# Sheet_1.net
KiCad netlist of a schematic drawn in Altium Designer
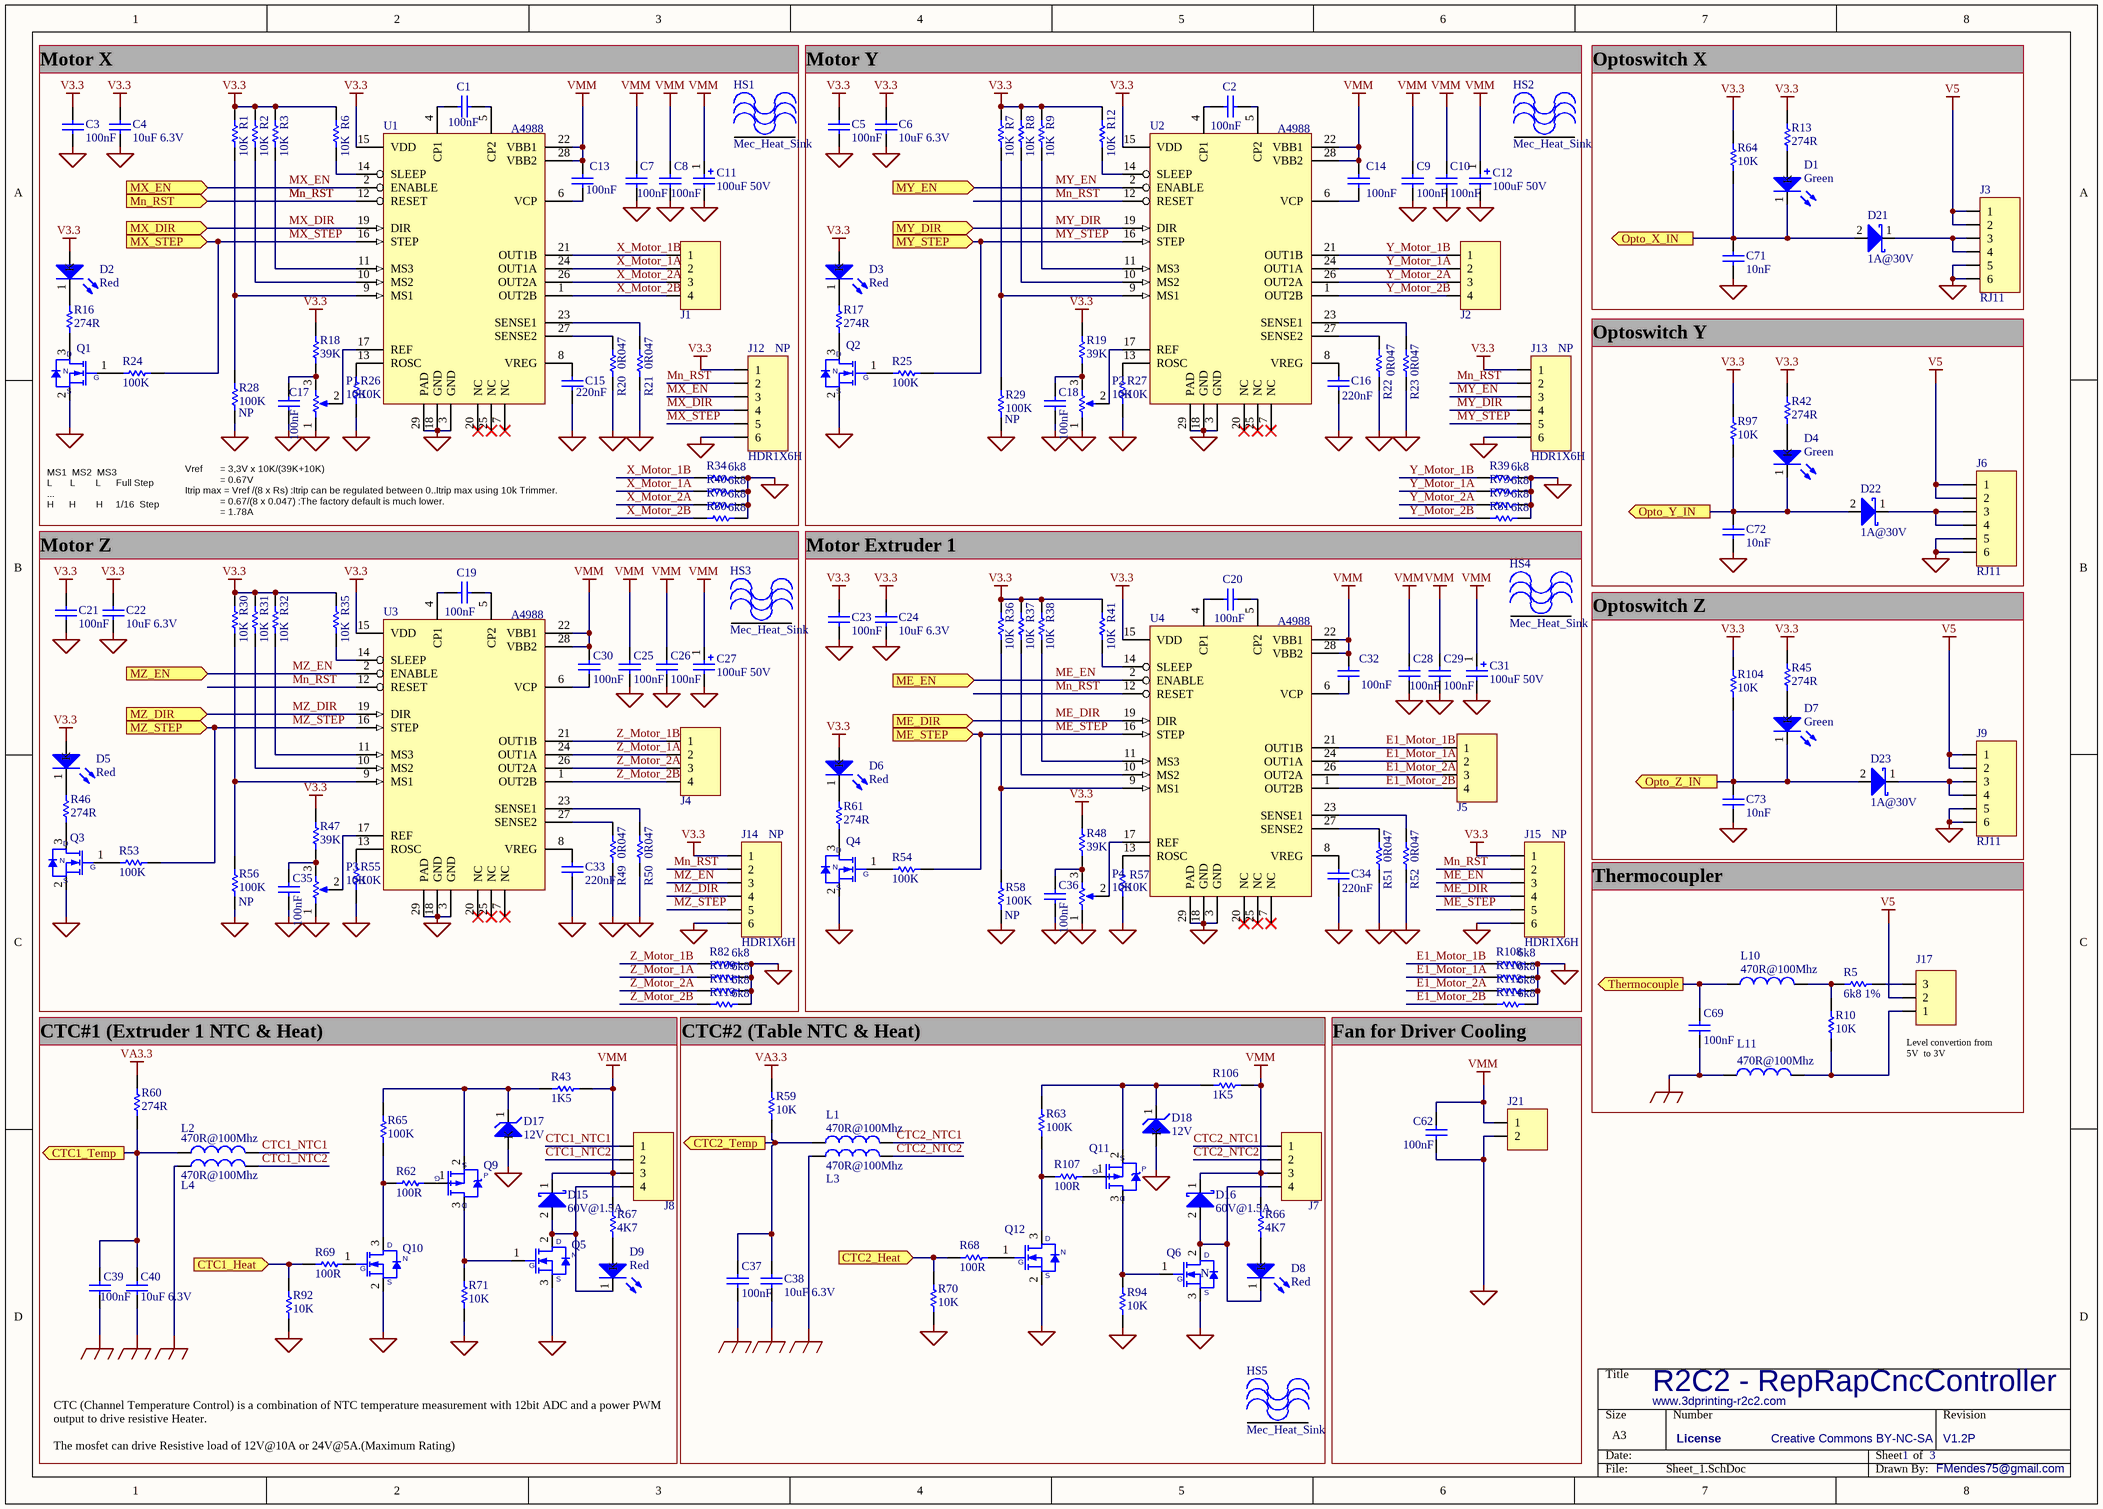
[diagram p0: Sheet_1.SchDoc]

(export (version "E")
  (design (tool "Eeschema 10.0.6"))
  (components
    (comp (ref "C1")
      (value "100nF")
      (footprint "CAPC1608M")
      (description "Capacitor - MLCC; 0603; NP0; 50V")
      (fields (field (name "PART NUMBER") "10000054") (field (name "MANUFACTURER") "Multicomp"))
      (libsource (lib "HB_DB_Components") (part "Cap Non Pol"))
    )
    (comp (ref "C2")
      (value "100nF")
      (footprint "CAPC1608M")
      (description "Capacitor Non Polarized")
      (fields (field (name "PART NUMBER") "10000054") (field (name "MANUFACTURER") "Multicomp"))
      (libsource (lib "HB_DB_Components") (part "Cap Non Pol"))
    )
    (comp (ref "C3")
      (value "100nF")
      (footprint "CAPC1608M")
      (description "Capacitor - MLCC; 0603; NP0; 50V")
      (fields (field (name "PART NUMBER") "10000054") (field (name "MANUFACTURER") "Multicomp"))
      (libsource (lib "HB_DB_Components") (part "Cap Non Pol"))
    )
    (comp (ref "C4")
      (value "10uF 6.3V")
      (footprint "CAPC2012M")
      (description "Capacitor - MLCC; 0805; Y5V; 10UF; 6.3V")
      (fields (field (name "PART NUMBER") "10000001") (field (name "MANUFACTURER") "MULTICOMP"))
      (libsource (lib "HB_DB_Components") (part "Cap Non Pol"))
    )
    (comp (ref "C5")
      (value "100nF")
      (footprint "CAPC1608M")
      (description "Capacitor - MLCC; 0603; NP0; 50V")
      (fields (field (name "PART NUMBER") "10000054") (field (name "MANUFACTURER") "Multicomp"))
      (libsource (lib "HB_DB_Components") (part "Cap Non Pol"))
    )
    (comp (ref "C6")
      (value "10uF 6.3V")
      (footprint "CAPC2012M")
      (description "Capacitor - MLCC; 0805; Y5V; 10UF; 6.3V")
      (fields (field (name "PART NUMBER") "10000001") (field (name "MANUFACTURER") "MULTICOMP"))
      (libsource (lib "HB_DB_Components") (part "Cap Non Pol"))
    )
    (comp (ref "C7")
      (value "100nF")
      (footprint "CAPC1608M")
      (description "Capacitor - MLCC; 0603; NP0; 50V")
      (fields (field (name "PART NUMBER") "10000054") (field (name "MANUFACTURER") "Multicomp"))
      (libsource (lib "HB_DB_Components") (part "Cap Non Pol"))
    )
    (comp (ref "C8")
      (value "100nF")
      (footprint "CAPC1608M")
      (description "Capacitor - MLCC; 0603; NP0; 50V")
      (fields (field (name "PART NUMBER") "10000054") (field (name "MANUFACTURER") "Multicomp"))
      (libsource (lib "HB_DB_Components") (part "Cap Non Pol"))
    )
    (comp (ref "C9")
      (value "100nF")
      (footprint "CAPC1608M")
      (description "Capacitor - MLCC; 0603; NP0; 50V")
      (fields (field (name "PART NUMBER") "10000054") (field (name "MANUFACTURER") "Multicomp"))
      (libsource (lib "HB_DB_Components") (part "Cap Non Pol"))
    )
    (comp (ref "C10")
      (value "100nF")
      (footprint "CAPC1608M")
      (description "Capacitor - MLCC; 0603; NP0; 50V")
      (fields (field (name "PART NUMBER") "10000054") (field (name "MANUFACTURER") "Multicomp"))
      (libsource (lib "HB_DB_Components") (part "Cap Non Pol"))
    )
    (comp (ref "C11")
      (value "100uF 50V")
      (footprint "CAPAE100X100M")
      (description "Capacitor - Al. Electrolytic; 100UF; 50V")
      (fields (field (name "PART NUMBER") "10000069") (field (name "MANUFACTURER") "Vishay"))
      (libsource (lib "HB_DB_Components") (part "Cap Pol"))
    )
    (comp (ref "C12")
      (value "100uF 50V")
      (footprint "CAPAE100X100M")
      (description "Capacitor - Al. Electrolytic; 100UF; 50V")
      (fields (field (name "PART NUMBER") "10000069") (field (name "MANUFACTURER") "Vishay"))
      (libsource (lib "HB_DB_Components") (part "Cap Pol"))
    )
    (comp (ref "C13")
      (value "100nF")
      (footprint "CAPC1608M")
      (description "Capacitor - MLCC; 0603; NP0; 50V")
      (fields (field (name "PART NUMBER") "10000054") (field (name "MANUFACTURER") "Multicomp"))
      (libsource (lib "HB_DB_Components") (part "Cap Non Pol"))
    )
    (comp (ref "C14")
      (value "100nF")
      (footprint "CAPC1608M")
      (description "Capacitor - MLCC; 0603; NP0; 50V")
      (fields (field (name "PART NUMBER") "10000054") (field (name "MANUFACTURER") "Multicomp"))
      (libsource (lib "HB_DB_Components") (part "Cap Non Pol"))
    )
    (comp (ref "C15")
      (value "220nF")
      (footprint "CAPC1608M")
      (description "Capacitor - MLCC; 0603; NP0; 50V")
      (fields (field (name "PART NUMBER") "10000059") (field (name "MANUFACTURER") "Multicomp"))
      (libsource (lib "HB_DB_Components") (part "Cap Non Pol"))
    )
    (comp (ref "C16")
      (value "220nF")
      (footprint "CAPC1608M")
      (description "Capacitor - MLCC; 0603; NP0; 50V")
      (fields (field (name "PART NUMBER") "10000059") (field (name "MANUFACTURER") "Multicomp"))
      (libsource (lib "HB_DB_Components") (part "Cap Non Pol"))
    )
    (comp (ref "C17")
      (value "100nF")
      (footprint "CAPC1608M")
      (description "Capacitor - MLCC; 0603; NP0; 50V")
      (fields (field (name "PART NUMBER") "10000054") (field (name "MANUFACTURER") "Multicomp"))
      (libsource (lib "HB_DB_Components") (part "Cap Non Pol"))
    )
    (comp (ref "C18")
      (value "100nF")
      (footprint "CAPC1608M")
      (description "Capacitor - MLCC; 0603; NP0; 50V")
      (fields (field (name "PART NUMBER") "10000054") (field (name "MANUFACTURER") "Multicomp"))
      (libsource (lib "HB_DB_Components") (part "Cap Non Pol"))
    )
    (comp (ref "C19")
      (value "100nF")
      (footprint "CAPC1608M")
      (description "Capacitor - MLCC; 0603; NP0; 50V")
      (fields (field (name "PART NUMBER") "10000054") (field (name "MANUFACTURER") "Multicomp"))
      (libsource (lib "HB_DB_Components") (part "Cap Non Pol"))
    )
    (comp (ref "C20")
      (value "100nF")
      (footprint "CAPC1608M")
      (description "Capacitor Non Polarized")
      (fields (field (name "PART NUMBER") "10000054") (field (name "MANUFACTURER") "Multicomp"))
      (libsource (lib "HB_DB_Components") (part "Cap Non Pol"))
    )
    (comp (ref "C21")
      (value "100nF")
      (footprint "CAPC1608M")
      (description "Capacitor - MLCC; 0603; NP0; 50V")
      (fields (field (name "PART NUMBER") "10000054") (field (name "MANUFACTURER") "Multicomp"))
      (libsource (lib "HB_DB_Components") (part "Cap Non Pol"))
    )
    (comp (ref "C22")
      (value "10uF 6.3V")
      (footprint "CAPC2012M")
      (description "Capacitor - MLCC; 0805; Y5V; 10UF; 6.3V")
      (fields (field (name "PART NUMBER") "10000001") (field (name "MANUFACTURER") "MULTICOMP"))
      (libsource (lib "HB_DB_Components") (part "Cap Non Pol"))
    )
    (comp (ref "C23")
      (value "100nF")
      (footprint "CAPC1608M")
      (description "Capacitor - MLCC; 0603; NP0; 50V")
      (fields (field (name "PART NUMBER") "10000054") (field (name "MANUFACTURER") "Multicomp"))
      (libsource (lib "HB_DB_Components") (part "Cap Non Pol"))
    )
    (comp (ref "C24")
      (value "10uF 6.3V")
      (footprint "CAPC2012M")
      (description "Capacitor - MLCC; 0805; Y5V; 10UF; 6.3V")
      (fields (field (name "PART NUMBER") "10000001") (field (name "MANUFACTURER") "MULTICOMP"))
      (libsource (lib "HB_DB_Components") (part "Cap Non Pol"))
    )
    (comp (ref "C25")
      (value "100nF")
      (footprint "CAPC1608M")
      (description "Capacitor - MLCC; 0603; NP0; 50V")
      (fields (field (name "PART NUMBER") "10000054") (field (name "MANUFACTURER") "Multicomp"))
      (libsource (lib "HB_DB_Components") (part "Cap Non Pol"))
    )
    (comp (ref "C26")
      (value "100nF")
      (footprint "CAPC1608M")
      (description "Capacitor - MLCC; 0603; NP0; 50V")
      (fields (field (name "PART NUMBER") "10000054") (field (name "MANUFACTURER") "Multicomp"))
      (libsource (lib "HB_DB_Components") (part "Cap Non Pol"))
    )
    (comp (ref "C27")
      (value "100uF 50V")
      (footprint "CAPAE100X100M")
      (description "Capacitor - Al. Electrolytic; 100UF; 50V")
      (fields (field (name "PART NUMBER") "10000069") (field (name "MANUFACTURER") "Vishay"))
      (libsource (lib "HB_DB_Components") (part "Cap Pol"))
    )
    (comp (ref "C28")
      (value "100nF")
      (footprint "CAPC1608M")
      (description "Capacitor - MLCC; 0603; NP0; 50V")
      (fields (field (name "PART NUMBER") "10000054") (field (name "MANUFACTURER") "Multicomp"))
      (libsource (lib "HB_DB_Components") (part "Cap Non Pol"))
    )
    (comp (ref "C29")
      (value "100nF")
      (footprint "CAPC1608M")
      (description "Capacitor - MLCC; 0603; NP0; 50V")
      (fields (field (name "PART NUMBER") "10000054") (field (name "MANUFACTURER") "Multicomp"))
      (libsource (lib "HB_DB_Components") (part "Cap Non Pol"))
    )
    (comp (ref "C30")
      (value "100nF")
      (footprint "CAPC1608M")
      (description "Capacitor - MLCC; 0603; NP0; 50V")
      (fields (field (name "PART NUMBER") "10000054") (field (name "MANUFACTURER") "Multicomp"))
      (libsource (lib "HB_DB_Components") (part "Cap Non Pol"))
    )
    (comp (ref "C31")
      (value "100uF 50V")
      (footprint "CAPAE100X100M")
      (description "Capacitor - Al. Electrolytic; 100UF; 50V")
      (fields (field (name "PART NUMBER") "10000069") (field (name "MANUFACTURER") "Vishay"))
      (libsource (lib "HB_DB_Components") (part "Cap Pol"))
    )
    (comp (ref "C32")
      (value "100nF")
      (footprint "CAPC1608M")
      (description "Capacitor - MLCC; 0603; NP0; 50V")
      (fields (field (name "PART NUMBER") "10000054") (field (name "MANUFACTURER") "Multicomp"))
      (libsource (lib "HB_DB_Components") (part "Cap Non Pol"))
    )
    (comp (ref "C33")
      (value "220nF")
      (footprint "CAPC1608M")
      (description "Capacitor - MLCC; 0603; NP0; 50V")
      (fields (field (name "PART NUMBER") "10000059") (field (name "MANUFACTURER") "Multicomp"))
      (libsource (lib "HB_DB_Components") (part "Cap Non Pol"))
    )
    (comp (ref "C34")
      (value "220nF")
      (footprint "CAPC1608M")
      (description "Capacitor - MLCC; 0603; NP0; 50V")
      (fields (field (name "PART NUMBER") "10000059") (field (name "MANUFACTURER") "Multicomp"))
      (libsource (lib "HB_DB_Components") (part "Cap Non Pol"))
    )
    (comp (ref "C35")
      (value "100nF")
      (footprint "CAPC1608M")
      (description "Capacitor - MLCC; 0603; NP0; 50V")
      (fields (field (name "PART NUMBER") "10000054") (field (name "MANUFACTURER") "Multicomp"))
      (libsource (lib "HB_DB_Components") (part "Cap Non Pol"))
    )
    (comp (ref "C36")
      (value "100nF")
      (footprint "CAPC1608M")
      (description "Capacitor - MLCC; 0603; NP0; 50V")
      (fields (field (name "PART NUMBER") "10000054") (field (name "MANUFACTURER") "Multicomp"))
      (libsource (lib "HB_DB_Components") (part "Cap Non Pol"))
    )
    (comp (ref "C37")
      (value "100nF")
      (footprint "CAPC1608M")
      (description "Capacitor - MLCC; 0603; NP0; 50V")
      (fields (field (name "PART NUMBER") "10000054") (field (name "MANUFACTURER") "Multicomp"))
      (libsource (lib "HB_DB_Components") (part "Cap Non Pol"))
    )
    (comp (ref "C38")
      (value "10uF 6.3V")
      (footprint "CAPC2012M")
      (description "Capacitor - MLCC; 0805; Y5V; 10UF; 6.3V")
      (fields (field (name "PART NUMBER") "10000001") (field (name "MANUFACTURER") "MULTICOMP"))
      (libsource (lib "HB_DB_Components") (part "Cap Non Pol"))
    )
    (comp (ref "C39")
      (value "100nF")
      (footprint "CAPC1608M")
      (description "Capacitor - MLCC; 0603; NP0; 50V")
      (fields (field (name "PART NUMBER") "10000054") (field (name "MANUFACTURER") "Multicomp"))
      (libsource (lib "HB_DB_Components") (part "Cap Non Pol"))
    )
    (comp (ref "C40")
      (value "10uF 6.3V")
      (footprint "CAPC2012M")
      (description "Capacitor - MLCC; 0805; Y5V; 10UF; 6.3V")
      (fields (field (name "PART NUMBER") "10000001") (field (name "MANUFACTURER") "MULTICOMP"))
      (libsource (lib "HB_DB_Components") (part "Cap Non Pol"))
    )
    (comp (ref "C62")
      (value "100nF")
      (footprint "CAPC1608M")
      (description "Capacitor - MLCC; 0603; NP0; 50V")
      (fields (field (name "PART NUMBER") "10000054") (field (name "MANUFACTURER") "Multicomp"))
      (libsource (lib "HB_DB_Components") (part "Cap Non Pol"))
    )
    (comp (ref "C69")
      (value "100nF")
      (footprint "CAPC1608M")
      (description "Capacitor - MLCC; 0603; NP0; 50V")
      (fields (field (name "PART NUMBER") "10000054") (field (name "MANUFACTURER") "Multicomp"))
      (libsource (lib "HB_DB_Components") (part "Cap Non Pol"))
    )
    (comp (ref "C71")
      (value "10nF")
      (footprint "CAPC1608M")
      (description "Capacitor - MLCC; 0603; NP0; 50V")
      (fields (field (name "PART NUMBER") "10000057") (field (name "MANUFACTURER") "Multicomp"))
      (libsource (lib "HB_DB_Components") (part "Cap Non Pol"))
    )
    (comp (ref "C72")
      (value "10nF")
      (footprint "CAPC1608M")
      (description "Capacitor - MLCC; 0603; NP0; 50V")
      (fields (field (name "PART NUMBER") "10000057") (field (name "MANUFACTURER") "Multicomp"))
      (libsource (lib "HB_DB_Components") (part "Cap Non Pol"))
    )
    (comp (ref "C73")
      (value "10nF")
      (footprint "CAPC1608M")
      (description "Capacitor - MLCC; 0603; NP0; 50V")
      (fields (field (name "PART NUMBER") "10000057") (field (name "MANUFACTURER") "Multicomp"))
      (libsource (lib "HB_DB_Components") (part "Cap Non Pol"))
    )
    (comp (ref "D1")
      (value "Green")
      (footprint "LEDM_3216X12M")
      (description "Led - 1206; Green OSRAM")
      (fields (field (name "PART NUMBER") "10000008") (field (name "MANUFACTURER") "OSRAM"))
      (libsource (lib "HB_DB_Components") (part "LED"))
    )
    (comp (ref "D2")
      (value "Red")
      (footprint "LEDM_3216X12M")
      (description "Led - 1206; Red")
      (fields (field (name "PART NUMBER") "10000089"))
      (libsource (lib "HB_DB_Components") (part "LED"))
    )
    (comp (ref "D3")
      (value "Red")
      (footprint "LEDM_3216X12M")
      (description "Led - 1206; Red")
      (fields (field (name "PART NUMBER") "10000089"))
      (libsource (lib "HB_DB_Components") (part "LED"))
    )
    (comp (ref "D4")
      (value "Green")
      (footprint "LEDM_3216X12M")
      (description "Led - 1206; Green OSRAM")
      (fields (field (name "PART NUMBER") "10000008") (field (name "MANUFACTURER") "OSRAM"))
      (libsource (lib "HB_DB_Components") (part "LED"))
    )
    (comp (ref "D5")
      (value "Red")
      (footprint "LEDM_3216X12M")
      (description "Led - 1206; Red")
      (fields (field (name "PART NUMBER") "10000089"))
      (libsource (lib "HB_DB_Components") (part "LED"))
    )
    (comp (ref "D6")
      (value "Red")
      (footprint "LEDM_3216X12M")
      (description "Led - 1206; Red")
      (fields (field (name "PART NUMBER") "10000089"))
      (libsource (lib "HB_DB_Components") (part "LED"))
    )
    (comp (ref "D7")
      (value "Green")
      (footprint "LEDM_3216X12M")
      (description "Led - 1206; Green OSRAM")
      (fields (field (name "PART NUMBER") "10000008") (field (name "MANUFACTURER") "OSRAM"))
      (libsource (lib "HB_DB_Components") (part "LED"))
    )
    (comp (ref "D8")
      (value "Red")
      (footprint "LEDM_3216X12M")
      (description "Led - 1206; Red")
      (fields (field (name "PART NUMBER") "10000089"))
      (libsource (lib "HB_DB_Components") (part "LED"))
    )
    (comp (ref "D9")
      (value "Red")
      (footprint "LEDM_3216X12M")
      (description "Led - 1206; Red")
      (fields (field (name "PART NUMBER") "10000089"))
      (libsource (lib "HB_DB_Components") (part "LED"))
    )
    (comp (ref "D15")
      (value "60V@1.5A")
      (footprint "SMA")
      (description "Diode - Schottky; 1.5A; 60V")
      (fields (field (name "PART NUMBER") "10000010") (field (name "MANUFACTURER") "VISHAY"))
      (libsource (lib "HB_DB_Components") (part "D Schottky"))
    )
    (comp (ref "D16")
      (value "60V@1.5A")
      (footprint "SMA")
      (description "Diode - Schottky; 1.5A; 60V")
      (fields (field (name "PART NUMBER") "10000010") (field (name "MANUFACTURER") "VISHAY"))
      (libsource (lib "HB_DB_Components") (part "D Schottky"))
    )
    (comp (ref "D17")
      (value "12V")
      (footprint "SOD323")
      (description "Diode - Zener; 0.4W; 12V")
      (fields (field (name "PART NUMBER") "10000088") (field (name "MANUFACTURER") "NXP"))
      (libsource (lib "HB_DB_Components") (part "D Zener"))
    )
    (comp (ref "D18")
      (value "12V")
      (footprint "SOD323")
      (description "Diode - Zener; 0.4W; 12V")
      (fields (field (name "PART NUMBER") "10000088") (field (name "MANUFACTURER") "NXP"))
      (libsource (lib "HB_DB_Components") (part "D Zener"))
    )
    (comp (ref "D21")
      (value "1A@30V")
      (footprint "SOD323")
      (description "Diode - Schottky; 30V; 1A;")
      (fields (field (name "PART NUMBER") "10000085") (field (name "MANUFACTURER") "NXP"))
      (libsource (lib "HB_DB_Components") (part "D Schottky"))
    )
    (comp (ref "D22")
      (value "1A@30V")
      (footprint "SOD323")
      (description "Diode - Schottky; 30V; 1A;")
      (fields (field (name "PART NUMBER") "10000085") (field (name "MANUFACTURER") "NXP"))
      (libsource (lib "HB_DB_Components") (part "D Schottky"))
    )
    (comp (ref "D23")
      (value "1A@30V")
      (footprint "SOD323")
      (description "Diode - Schottky; 30V; 1A;")
      (fields (field (name "PART NUMBER") "10000085") (field (name "MANUFACTURER") "NXP"))
      (libsource (lib "HB_DB_Components") (part "D Schottky"))
    )
    (comp (ref "HS1")
      (value "Mec_Heat_Sink")
      (footprint "HS_180x130x50")
      (description "Heat Sink - IC stiker")
      (fields (field (name "PART NUMBER") "10000090"))
      (libsource (lib "HB_DB_Components") (part "Mec_Heat_Sink"))
    )
    (comp (ref "HS2")
      (value "Mec_Heat_Sink")
      (footprint "HS_180x130x50")
      (description "Heat Sink - IC stiker")
      (fields (field (name "PART NUMBER") "10000090"))
      (libsource (lib "HB_DB_Components") (part "Mec_Heat_Sink"))
    )
    (comp (ref "HS3")
      (value "Mec_Heat_Sink")
      (footprint "HS_180x130x50")
      (description "Heat Sink - IC stiker")
      (fields (field (name "PART NUMBER") "10000090"))
      (libsource (lib "HB_DB_Components") (part "Mec_Heat_Sink"))
    )
    (comp (ref "HS4")
      (value "Mec_Heat_Sink")
      (footprint "HS_180x130x50")
      (description "Heat Sink - IC stiker")
      (fields (field (name "PART NUMBER") "10000090"))
      (libsource (lib "HB_DB_Components") (part "Mec_Heat_Sink"))
    )
    (comp (ref "HS5")
      (value "Mec_Heat_Sink")
      (footprint "FK_244_13_D2PAK")
      (description "Heat Sink - For D2PAK")
      (fields (field (name "PART NUMBER") "10000091") (field (name "MANUFACTURER") "Fischer Elektronik"))
      (libsource (lib "HB_DB_Components") (part "Mec_Heat_Sink"))
    )
    (comp (ref "J1")
      (value "Con 4")
      (footprint "WEIDMULLER_SL-5.08-04-90B")
      (description "Connector - Header male; Screw; 4way; Hor.")
      (fields (field (name "PART NUMBER") "10000023") (field (name "MANUFACTURER") "WEIDMULLER"))
      (libsource (lib "HB_DB_Components") (part "Con 4"))
    )
    (comp (ref "J2")
      (value "Con 4")
      (footprint "WEIDMULLER_SL-5.08-04-90B")
      (description "Connector - Header male; Screw; 4way; Hor.")
      (fields (field (name "PART NUMBER") "10000023") (field (name "MANUFACTURER") "WEIDMULLER"))
      (libsource (lib "HB_DB_Components") (part "Con 4"))
    )
    (comp (ref "J3")
      (value "RJ11")
      (footprint "MOLEX_95022-2667")
      (description "Connector - PCB; RJ11; 6/4 Low Profile; Hor.")
      (fields (field (name "PART NUMBER") "10000062") (field (name "MANUFACTURER") "Molex"))
      (libsource (lib "HB_DB_Components") (part "Con 6"))
    )
    (comp (ref "J4")
      (value "Con 4")
      (footprint "WEIDMULLER_SL-5.08-04-90B")
      (description "Connector - Header male; Screw; 4way; Hor.")
      (fields (field (name "PART NUMBER") "10000023") (field (name "MANUFACTURER") "WEIDMULLER"))
      (libsource (lib "HB_DB_Components") (part "Con 4"))
    )
    (comp (ref "J5")
      (value "Con 4")
      (footprint "WEIDMULLER_SL-5.08-04-90B")
      (description "Connector - Header male; Screw; 4way; Hor.")
      (fields (field (name "PART NUMBER") "10000023") (field (name "MANUFACTURER") "WEIDMULLER"))
      (libsource (lib "HB_DB_Components") (part "Con 4"))
    )
    (comp (ref "J6")
      (value "RJ11")
      (footprint "MOLEX_95022-2667")
      (description "Connector - PCB; RJ11; 6/4 Low Profile; Hor.")
      (fields (field (name "PART NUMBER") "10000062") (field (name "MANUFACTURER") "Molex"))
      (libsource (lib "HB_DB_Components") (part "Con 6"))
    )
    (comp (ref "J7")
      (value "Con 4")
      (footprint "WEIDMULLER_SL-5.08-04-90B")
      (description "Connector - Header male; Screw; 4way; Hor.")
      (fields (field (name "PART NUMBER") "10000023") (field (name "MANUFACTURER") "WEIDMULLER"))
      (libsource (lib "HB_DB_Components") (part "Con 4"))
    )
    (comp (ref "J8")
      (value "Con 4")
      (footprint "WEIDMULLER_SL-5.08-04-90B")
      (description "Connector - Header male; Screw; 4way; Hor.")
      (fields (field (name "PART NUMBER") "10000023") (field (name "MANUFACTURER") "WEIDMULLER"))
      (libsource (lib "HB_DB_Components") (part "Con 4"))
    )
    (comp (ref "J9")
      (value "RJ11")
      (footprint "MOLEX_95022-2667")
      (description "Connector - PCB; RJ11; 6/4 Low Profile; Hor.")
      (fields (field (name "PART NUMBER") "10000062") (field (name "MANUFACTURER") "Molex"))
      (libsource (lib "HB_DB_Components") (part "Con 6"))
    )
    (comp (ref "J12")
      (value "HDR1X6H")
      (footprint "HDR1X6")
      (description "Connector - Header 1x6; Vert..")
      (fields (field (name "PART NUMBER") "10000093") (field (name "POPULATE") "NP"))
      (libsource (lib "HB_DB_Components") (part "Con 6"))
    )
    (comp (ref "J13")
      (value "HDR1X6H")
      (footprint "HDR1X6")
      (description "Connector - Header 1x6; Vert..")
      (fields (field (name "PART NUMBER") "10000093") (field (name "POPULATE") "NP"))
      (libsource (lib "HB_DB_Components") (part "Con 6"))
    )
    (comp (ref "J14")
      (value "HDR1X6H")
      (footprint "HDR1X6")
      (description "Connector - Header 1x6; Vert..")
      (fields (field (name "PART NUMBER") "10000093") (field (name "POPULATE") "NP"))
      (libsource (lib "HB_DB_Components") (part "Con 6"))
    )
    (comp (ref "J15")
      (value "HDR1X6H")
      (footprint "HDR1X6")
      (description "Connector - Header 1x6; Vert..")
      (fields (field (name "PART NUMBER") "10000093") (field (name "POPULATE") "NP"))
      (libsource (lib "HB_DB_Components") (part "Con 6"))
    )
    (comp (ref "J17")
      (value "Con 3")
      (footprint "phoenix-contact_smkdsn-5.08")
      (description "Terminal Block")
      (fields (field (name "PART NUMBER") "10000095") (field (name "MANUFACTURER") "Phoenix_Contact"))
      (libsource (lib "HB_DB_Components") (part "Con 3"))
    )
    (comp (ref "J21")
      (value "Con 2")
      (footprint "MOLEX_22-29-2021")
      (description "Connector - PCB; Header; SQ Pin, 2 way; 2.54mm; Vert")
      (fields (field (name "PART NUMBER") "10000097") (field (name "MANUFACTURER") "Molex"))
      (libsource (lib "HB_DB_Components") (part "Con 2"))
    )
    (comp (ref "L1")
      (value "470R@100Mhz")
      (footprint "INDC1608M")
      (description "Ferrite Bead - 470OHM; 0603")
      (fields (field (name "PART NUMBER") "10000032") (field (name "MANUFACTURER") "MURATA"))
      (libsource (lib "HB_DB_Components") (part "Ind"))
    )
    (comp (ref "L2")
      (value "470R@100Mhz")
      (footprint "INDC1608M")
      (description "Ferrite Bead - 470OHM; 0603")
      (fields (field (name "PART NUMBER") "10000032") (field (name "MANUFACTURER") "MURATA"))
      (libsource (lib "HB_DB_Components") (part "Ind"))
    )
    (comp (ref "L3")
      (value "470R@100Mhz")
      (footprint "INDC1608M")
      (description "Ferrite Bead - 470OHM; 0603")
      (fields (field (name "PART NUMBER") "10000032") (field (name "MANUFACTURER") "MURATA"))
      (libsource (lib "HB_DB_Components") (part "Ind"))
    )
    (comp (ref "L4")
      (value "470R@100Mhz")
      (footprint "INDC1608M")
      (description "Ferrite Bead - 470OHM; 0603")
      (fields (field (name "PART NUMBER") "10000032") (field (name "MANUFACTURER") "MURATA"))
      (libsource (lib "HB_DB_Components") (part "Ind"))
    )
    (comp (ref "L10")
      (value "470R@100Mhz")
      (footprint "INDC1608M")
      (description "Ferrite Bead - 470OHM; 0603")
      (fields (field (name "PART NUMBER") "10000032") (field (name "MANUFACTURER") "MURATA"))
      (libsource (lib "HB_DB_Components") (part "Ind"))
    )
    (comp (ref "L11")
      (value "470R@100Mhz")
      (footprint "INDC1608M")
      (description "Ferrite Bead - 470OHM; 0603")
      (fields (field (name "PART NUMBER") "10000032") (field (name "MANUFACTURER") "MURATA"))
      (libsource (lib "HB_DB_Components") (part "Ind"))
    )
    (comp (ref "P1")
      (value "10K")
      (footprint "Trimmer_14")
      (description "Resistor - Trimmer; 1/4\"; 10K")
      (fields (field (name "PART NUMBER") "10000092") (field (name "MANUFACTURER") "Bourns"))
      (libsource (lib "HB_DB_Components") (part "Res Pot"))
    )
    (comp (ref "P2")
      (value "10K")
      (footprint "Trimmer_14")
      (description "Resistor - Trimmer; 1/4\"; 10K")
      (fields (field (name "PART NUMBER") "10000092") (field (name "MANUFACTURER") "Bourns"))
      (libsource (lib "HB_DB_Components") (part "Res Pot"))
    )
    (comp (ref "P3")
      (value "10K")
      (footprint "Trimmer_14")
      (description "Resistor - Trimmer; 1/4\"; 10K")
      (fields (field (name "PART NUMBER") "10000092") (field (name "MANUFACTURER") "Bourns"))
      (libsource (lib "HB_DB_Components") (part "Res Pot"))
    )
    (comp (ref "P4")
      (value "10K")
      (footprint "Trimmer_14")
      (description "Resistor - Trimmer; 1/4\"; 10K")
      (fields (field (name "PART NUMBER") "10000092") (field (name "MANUFACTURER") "Bourns"))
      (libsource (lib "HB_DB_Components") (part "Res Pot"))
    )
    (comp (ref "Q1")
      (value "N")
      (footprint "SOT323-3AM")
      (description "Mosfet - N; 60V; 0.3A;")
      (fields (field (name "PART NUMBER") "10000039") (field (name "MANUFACTURER") "NXP"))
      (libsource (lib "HB_DB_Components") (part "Q MOSFET-N"))
    )
    (comp (ref "Q2")
      (value "N")
      (footprint "SOT323-3AM")
      (description "Mosfet - N; 60V; 0.3A;")
      (fields (field (name "PART NUMBER") "10000039") (field (name "MANUFACTURER") "NXP"))
      (libsource (lib "HB_DB_Components") (part "Q MOSFET-N"))
    )
    (comp (ref "Q3")
      (value "N")
      (footprint "SOT323-3AM")
      (description "Mosfet - N; 60V; 0.3A;")
      (fields (field (name "PART NUMBER") "10000039") (field (name "MANUFACTURER") "NXP"))
      (libsource (lib "HB_DB_Components") (part "Q MOSFET-N"))
    )
    (comp (ref "Q4")
      (value "N")
      (footprint "SOT323-3AM")
      (description "Mosfet - N; 60V; 0.3A;")
      (fields (field (name "PART NUMBER") "10000039") (field (name "MANUFACTURER") "NXP"))
      (libsource (lib "HB_DB_Components") (part "Q MOSFET-N"))
    )
    (comp (ref "Q5")
      (value "N")
      (footprint "D2PAK")
      (description "N-channel Enhancement Mode Field-effect Transistor (123/gds)")
      (fields (field (name "PART NUMBER") "10000078") (field (name "MANUFACTURER") "IR"))
      (libsource (lib "HB_DB_Components") (part "Q MOSFET-N_gds"))
    )
    (comp (ref "Q6")
      (value "N")
      (footprint "D2PAK")
      (description "N-channel Enhancement Mode Field-effect Transistor (123/gds)")
      (fields (field (name "PART NUMBER") "10000078") (field (name "MANUFACTURER") "IR"))
      (libsource (lib "HB_DB_Components") (part "Q MOSFET-N_gds"))
    )
    (comp (ref "Q9")
      (value "P")
      (footprint "SOT23-3M")
      (description "Mosfet - Power; Vdss=-30v; Rds=0.60; Id=-0.6A")
      (fields (field (name "PART NUMBER") "10000076") (field (name "MANUFACTURER") "IR"))
      (libsource (lib "HB_DB_Components") (part "MOS-P"))
    )
    (comp (ref "Q10")
      (value "N")
      (footprint "SOT323-3AM")
      (description "Mosfet - N; 60V; 0.3A;")
      (fields (field (name "PART NUMBER") "10000039") (field (name "MANUFACTURER") "NXP"))
      (libsource (lib "HB_DB_Components") (part "Q MOSFET-N"))
    )
    (comp (ref "Q11")
      (value "P")
      (footprint "SOT23-3M")
      (description "Mosfet - Power; Vdss=-30v; Rds=0.60; Id=-0.6A")
      (fields (field (name "PART NUMBER") "10000076") (field (name "MANUFACTURER") "IR"))
      (libsource (lib "HB_DB_Components") (part "MOS-P"))
    )
    (comp (ref "Q12")
      (value "N")
      (footprint "SOT323-3AM")
      (description "Mosfet - N; 60V; 0.3A;")
      (fields (field (name "PART NUMBER") "10000039") (field (name "MANUFACTURER") "NXP"))
      (libsource (lib "HB_DB_Components") (part "Q MOSFET-N"))
    )
    (comp (ref "R1")
      (value "10K")
      (footprint "RESC1608M")
      (description "Resistor - 0603; 0.063W; 1%")
      (fields (field (name "PART NUMBER") "10000044") (field (name "MANUFACTURER") "Multicomp"))
      (libsource (lib "HB_DB_Components") (part "Res"))
    )
    (comp (ref "R2")
      (value "10K")
      (footprint "RESC1608M")
      (description "Resistor - 0603; 0.063W; 1%")
      (fields (field (name "PART NUMBER") "10000044") (field (name "MANUFACTURER") "Multicomp"))
      (libsource (lib "HB_DB_Components") (part "Res"))
    )
    (comp (ref "R3")
      (value "10K")
      (footprint "RESC1608M")
      (description "Resistor - 0603; 0.063W; 1%")
      (fields (field (name "PART NUMBER") "10000044") (field (name "MANUFACTURER") "Multicomp"))
      (libsource (lib "HB_DB_Components") (part "Res"))
    )
    (comp (ref "R5")
      (value "6k8 1%")
      (footprint "RESC1608M")
      (description "Resistor - 0603; 0.063W; 1%")
      (fields (field (name "PART NUMBER") "10000080") (field (name "MANUFACTURER") "Vishay"))
      (libsource (lib "HB_DB_Components") (part "Res"))
    )
    (comp (ref "R6")
      (value "10K")
      (footprint "RESC1608M")
      (description "Resistor - 0603; 0.063W; 1%")
      (fields (field (name "PART NUMBER") "10000044") (field (name "MANUFACTURER") "Multicomp"))
      (libsource (lib "HB_DB_Components") (part "Res"))
    )
    (comp (ref "R7")
      (value "10K")
      (footprint "RESC1608M")
      (description "Resistor - 0603; 0.063W; 1%")
      (fields (field (name "PART NUMBER") "10000044") (field (name "MANUFACTURER") "Multicomp"))
      (libsource (lib "HB_DB_Components") (part "Res"))
    )
    (comp (ref "R8")
      (value "10K")
      (footprint "RESC1608M")
      (description "Resistor - 0603; 0.063W; 1%")
      (fields (field (name "PART NUMBER") "10000044") (field (name "MANUFACTURER") "Multicomp"))
      (libsource (lib "HB_DB_Components") (part "Res"))
    )
    (comp (ref "R9")
      (value "10K")
      (footprint "RESC1608M")
      (description "Resistor - 0603; 0.063W; 1%")
      (fields (field (name "PART NUMBER") "10000044") (field (name "MANUFACTURER") "Multicomp"))
      (libsource (lib "HB_DB_Components") (part "Res"))
    )
    (comp (ref "R10")
      (value "10K")
      (footprint "RESC1608M")
      (description "Resistor")
      (fields (field (name "PART NUMBER") "10000044") (field (name "MANUFACTURER") "Multicomp"))
      (libsource (lib "HB_DB_Components") (part "Res"))
    )
    (comp (ref "R12")
      (value "10K")
      (footprint "RESC1608M")
      (description "Resistor - 0603; 0.063W; 1%")
      (fields (field (name "PART NUMBER") "10000044") (field (name "MANUFACTURER") "Multicomp"))
      (libsource (lib "HB_DB_Components") (part "Res"))
    )
    (comp (ref "R13")
      (value "274R")
      (footprint "RESC1608M")
      (description "Resistor - 0603; 0.063W; 1%")
      (fields (field (name "PART NUMBER") "10000041") (field (name "MANUFACTURER") "Multicomp"))
      (libsource (lib "HB_DB_Components") (part "Res"))
    )
    (comp (ref "R16")
      (value "274R")
      (footprint "RESC1608M")
      (description "Resistor - 0603; 0.063W; 1%")
      (fields (field (name "PART NUMBER") "10000041") (field (name "MANUFACTURER") "Multicomp"))
      (libsource (lib "HB_DB_Components") (part "Res"))
    )
    (comp (ref "R17")
      (value "274R")
      (footprint "RESC1608M")
      (description "Resistor - 0603; 0.063W; 1%")
      (fields (field (name "PART NUMBER") "10000041") (field (name "MANUFACTURER") "Multicomp"))
      (libsource (lib "HB_DB_Components") (part "Res"))
    )
    (comp (ref "R18")
      (value "39K")
      (footprint "RESC1608M")
      (description "Resistor - 0603; 0.063W; 1%")
      (fields (field (name "PART NUMBER") "10000087"))
      (libsource (lib "HB_DB_Components") (part "Res"))
    )
    (comp (ref "R19")
      (value "39K")
      (footprint "RESC1608M")
      (description "Resistor - 0603; 0.063W; 1%")
      (fields (field (name "PART NUMBER") "10000087"))
      (libsource (lib "HB_DB_Components") (part "Res"))
    )
    (comp (ref "R20")
      (value "0R047")
      (footprint "RESC3216M")
      (description "Resistor - 1206; 0.5W; 1%")
      (fields (field (name "PART NUMBER") "10000047") (field (name "MANUFACTURER") "YAGEO"))
      (libsource (lib "HB_DB_Components") (part "Res"))
    )
    (comp (ref "R21")
      (value "0R047")
      (footprint "RESC3216M")
      (description "Resistor - 1206; 0.5W; 1%")
      (fields (field (name "PART NUMBER") "10000047") (field (name "MANUFACTURER") "YAGEO"))
      (libsource (lib "HB_DB_Components") (part "Res"))
    )
    (comp (ref "R22")
      (value "0R047")
      (footprint "RESC3216M")
      (description "Resistor - 1206; 0.5W; 1%")
      (fields (field (name "PART NUMBER") "10000047") (field (name "MANUFACTURER") "YAGEO"))
      (libsource (lib "HB_DB_Components") (part "Res"))
    )
    (comp (ref "R23")
      (value "0R047")
      (footprint "RESC3216M")
      (description "Resistor - 1206; 0.5W; 1%")
      (fields (field (name "PART NUMBER") "10000047") (field (name "MANUFACTURER") "YAGEO"))
      (libsource (lib "HB_DB_Components") (part "Res"))
    )
    (comp (ref "R24")
      (value "100K")
      (footprint "RESC1608M")
      (description "Resistor - 0603; 0.063W; 1%")
      (fields (field (name "PART NUMBER") "10000045") (field (name "MANUFACTURER") "Multicomp"))
      (libsource (lib "HB_DB_Components") (part "Res"))
    )
    (comp (ref "R25")
      (value "100K")
      (footprint "RESC1608M")
      (description "Resistor - 0603; 0.063W; 1%")
      (fields (field (name "PART NUMBER") "10000045") (field (name "MANUFACTURER") "Multicomp"))
      (libsource (lib "HB_DB_Components") (part "Res"))
    )
    (comp (ref "R26")
      (value "10K")
      (footprint "RESC1608M")
      (description "Resistor - 0603; 0.063W; 1%")
      (fields (field (name "PART NUMBER") "10000044") (field (name "MANUFACTURER") "Multicomp"))
      (libsource (lib "HB_DB_Components") (part "Res"))
    )
    (comp (ref "R27")
      (value "10K")
      (footprint "RESC1608M")
      (description "Resistor - 0603; 0.063W; 1%")
      (fields (field (name "PART NUMBER") "10000044") (field (name "MANUFACTURER") "Multicomp"))
      (libsource (lib "HB_DB_Components") (part "Res"))
    )
    (comp (ref "R28")
      (value "100K")
      (footprint "RESC1608M")
      (description "Resistor - 0603; 0.063W; 1%")
      (fields
        (field (name "PART NUMBER") "10000045")
        (field (name "MANUFACTURER") "Multicomp")
        (field (name "POPULATE") "NP")
      )
      (libsource (lib "HB_DB_Components") (part "Res"))
    )
    (comp (ref "R29")
      (value "100K")
      (footprint "RESC1608M")
      (description "Resistor - 0603; 0.063W; 1%")
      (fields
        (field (name "PART NUMBER") "10000045")
        (field (name "MANUFACTURER") "Multicomp")
        (field (name "POPULATE") "NP")
      )
      (libsource (lib "HB_DB_Components") (part "Res"))
    )
    (comp (ref "R30")
      (value "10K")
      (footprint "RESC1608M")
      (description "Resistor - 0603; 0.063W; 1%")
      (fields (field (name "PART NUMBER") "10000044") (field (name "MANUFACTURER") "Multicomp"))
      (libsource (lib "HB_DB_Components") (part "Res"))
    )
    (comp (ref "R31")
      (value "10K")
      (footprint "RESC1608M")
      (description "Resistor - 0603; 0.063W; 1%")
      (fields (field (name "PART NUMBER") "10000044") (field (name "MANUFACTURER") "Multicomp"))
      (libsource (lib "HB_DB_Components") (part "Res"))
    )
    (comp (ref "R32")
      (value "10K")
      (footprint "RESC1608M")
      (description "Resistor - 0603; 0.063W; 1%")
      (fields (field (name "PART NUMBER") "10000044") (field (name "MANUFACTURER") "Multicomp"))
      (libsource (lib "HB_DB_Components") (part "Res"))
    )
    (comp (ref "R34")
      (value "6k8")
      (footprint "RESC2012L")
      (description "Resistor - 0805; 0.100W; 5%")
      (fields (field (name "PART NUMBER") "10000098"))
      (libsource (lib "HB_DB_Components") (part "Res"))
    )
    (comp (ref "R35")
      (value "10K")
      (footprint "RESC1608M")
      (description "Resistor - 0603; 0.063W; 1%")
      (fields (field (name "PART NUMBER") "10000044") (field (name "MANUFACTURER") "Multicomp"))
      (libsource (lib "HB_DB_Components") (part "Res"))
    )
    (comp (ref "R36")
      (value "10K")
      (footprint "RESC1608M")
      (description "Resistor - 0603; 0.063W; 1%")
      (fields (field (name "PART NUMBER") "10000044") (field (name "MANUFACTURER") "Multicomp"))
      (libsource (lib "HB_DB_Components") (part "Res"))
    )
    (comp (ref "R37")
      (value "10K")
      (footprint "RESC1608M")
      (description "Resistor - 0603; 0.063W; 1%")
      (fields (field (name "PART NUMBER") "10000044") (field (name "MANUFACTURER") "Multicomp"))
      (libsource (lib "HB_DB_Components") (part "Res"))
    )
    (comp (ref "R38")
      (value "10K")
      (footprint "RESC1608M")
      (description "Resistor - 0603; 0.063W; 1%")
      (fields (field (name "PART NUMBER") "10000044") (field (name "MANUFACTURER") "Multicomp"))
      (libsource (lib "HB_DB_Components") (part "Res"))
    )
    (comp (ref "R39")
      (value "6k8")
      (footprint "RESC2012L")
      (description "Resistor - 0805; 0.100W; 5%")
      (fields (field (name "PART NUMBER") "10000098"))
      (libsource (lib "HB_DB_Components") (part "Res"))
    )
    (comp (ref "R40")
      (value "6k8")
      (footprint "RESC2012L")
      (description "Resistor - 0805; 0.100W; 5%")
      (fields (field (name "PART NUMBER") "10000098"))
      (libsource (lib "HB_DB_Components") (part "Res"))
    )
    (comp (ref "R41")
      (value "10K")
      (footprint "RESC1608M")
      (description "Resistor - 0603; 0.063W; 1%")
      (fields (field (name "PART NUMBER") "10000044") (field (name "MANUFACTURER") "Multicomp"))
      (libsource (lib "HB_DB_Components") (part "Res"))
    )
    (comp (ref "R42")
      (value "274R")
      (footprint "RESC1608M")
      (description "Resistor - 0603; 0.063W; 1%")
      (fields (field (name "PART NUMBER") "10000041") (field (name "MANUFACTURER") "Multicomp"))
      (libsource (lib "HB_DB_Components") (part "Res"))
    )
    (comp (ref "R43")
      (value "1K5")
      (footprint "RESC1608M")
      (description "Resistor - 0603; 0.063W; 1%")
      (fields (field (name "PART NUMBER") "10000048") (field (name "MANUFACTURER") "Multicomp"))
      (libsource (lib "HB_DB_Components") (part "Res"))
    )
    (comp (ref "R45")
      (value "274R")
      (footprint "RESC1608M")
      (description "Resistor - 0603; 0.063W; 1%")
      (fields (field (name "PART NUMBER") "10000041") (field (name "MANUFACTURER") "Multicomp"))
      (libsource (lib "HB_DB_Components") (part "Res"))
    )
    (comp (ref "R46")
      (value "274R")
      (footprint "RESC1608M")
      (description "Resistor - 0603; 0.063W; 1%")
      (fields (field (name "PART NUMBER") "10000041") (field (name "MANUFACTURER") "Multicomp"))
      (libsource (lib "HB_DB_Components") (part "Res"))
    )
    (comp (ref "R47")
      (value "39K")
      (footprint "RESC1608M")
      (description "Resistor - 0603; 0.063W; 1%")
      (fields (field (name "PART NUMBER") "10000087"))
      (libsource (lib "HB_DB_Components") (part "Res"))
    )
    (comp (ref "R48")
      (value "39K")
      (footprint "RESC1608M")
      (description "Resistor - 0603; 0.063W; 1%")
      (fields (field (name "PART NUMBER") "10000087"))
      (libsource (lib "HB_DB_Components") (part "Res"))
    )
    (comp (ref "R49")
      (value "0R047")
      (footprint "RESC3216M")
      (description "Resistor - 1206; 0.5W; 1%")
      (fields (field (name "PART NUMBER") "10000047") (field (name "MANUFACTURER") "YAGEO"))
      (libsource (lib "HB_DB_Components") (part "Res"))
    )
    (comp (ref "R50")
      (value "0R047")
      (footprint "RESC3216M")
      (description "Resistor - 1206; 0.5W; 1%")
      (fields (field (name "PART NUMBER") "10000047") (field (name "MANUFACTURER") "YAGEO"))
      (libsource (lib "HB_DB_Components") (part "Res"))
    )
    (comp (ref "R51")
      (value "0R047")
      (footprint "RESC3216M")
      (description "Resistor - 1206; 0.5W; 1%")
      (fields (field (name "PART NUMBER") "10000047") (field (name "MANUFACTURER") "YAGEO"))
      (libsource (lib "HB_DB_Components") (part "Res"))
    )
    (comp (ref "R52")
      (value "0R047")
      (footprint "RESC3216M")
      (description "Resistor - 1206; 0.5W; 1%")
      (fields (field (name "PART NUMBER") "10000047") (field (name "MANUFACTURER") "YAGEO"))
      (libsource (lib "HB_DB_Components") (part "Res"))
    )
    (comp (ref "R53")
      (value "100K")
      (footprint "RESC1608M")
      (description "Resistor - 0603; 0.063W; 1%")
      (fields (field (name "PART NUMBER") "10000045") (field (name "MANUFACTURER") "Multicomp"))
      (libsource (lib "HB_DB_Components") (part "Res"))
    )
    (comp (ref "R54")
      (value "100K")
      (footprint "RESC1608M")
      (description "Resistor - 0603; 0.063W; 1%")
      (fields (field (name "PART NUMBER") "10000045") (field (name "MANUFACTURER") "Multicomp"))
      (libsource (lib "HB_DB_Components") (part "Res"))
    )
    (comp (ref "R55")
      (value "10K")
      (footprint "RESC1608M")
      (description "Resistor - 0603; 0.063W; 1%")
      (fields (field (name "PART NUMBER") "10000044") (field (name "MANUFACTURER") "Multicomp"))
      (libsource (lib "HB_DB_Components") (part "Res"))
    )
    (comp (ref "R56")
      (value "100K")
      (footprint "RESC1608M")
      (description "Resistor - 0603; 0.063W; 1%")
      (fields
        (field (name "PART NUMBER") "10000045")
        (field (name "MANUFACTURER") "Multicomp")
        (field (name "POPULATE") "NP")
      )
      (libsource (lib "HB_DB_Components") (part "Res"))
    )
    (comp (ref "R57")
      (value "10K")
      (footprint "RESC1608M")
      (description "Resistor - 0603; 0.063W; 1%")
      (fields (field (name "PART NUMBER") "10000044") (field (name "MANUFACTURER") "Multicomp"))
      (libsource (lib "HB_DB_Components") (part "Res"))
    )
    (comp (ref "R58")
      (value "100K")
      (footprint "RESC1608M")
      (description "Resistor - 0603; 0.063W; 1%")
      (fields
        (field (name "PART NUMBER") "10000045")
        (field (name "MANUFACTURER") "Multicomp")
        (field (name "POPULATE") "NP")
      )
      (libsource (lib "HB_DB_Components") (part "Res"))
    )
    (comp (ref "R59")
      (value "10K")
      (footprint "RESC1608M")
      (description "Resistor")
      (fields (field (name "PART NUMBER") "10000044") (field (name "MANUFACTURER") "Multicomp"))
      (libsource (lib "HB_DB_Components") (part "Res"))
    )
    (comp (ref "R60")
      (value "274R")
      (footprint "RESC1608M")
      (description "Resistor")
      (fields (field (name "PART NUMBER") "10000041") (field (name "MANUFACTURER") "Multicomp"))
      (libsource (lib "HB_DB_Components") (part "Res"))
    )
    (comp (ref "R61")
      (value "274R")
      (footprint "RESC1608M")
      (description "Resistor - 0603; 0.063W; 1%")
      (fields (field (name "PART NUMBER") "10000041") (field (name "MANUFACTURER") "Multicomp"))
      (libsource (lib "HB_DB_Components") (part "Res"))
    )
    (comp (ref "R62")
      (value "100R")
      (footprint "RESC1608M")
      (description "Resistor - 0603; 0.063W; 1%")
      (fields (field (name "PART NUMBER") "10000042") (field (name "MANUFACTURER") "Multicomp"))
      (libsource (lib "HB_DB_Components") (part "Res"))
    )
    (comp (ref "R63")
      (value "100K")
      (footprint "RESC1608M")
      (description "Resistor - 0603; 0.063W; 1%")
      (fields (field (name "PART NUMBER") "10000045") (field (name "MANUFACTURER") "Multicomp"))
      (libsource (lib "HB_DB_Components") (part "Res"))
    )
    (comp (ref "R64")
      (value "10K")
      (footprint "RESC1608M")
      (description "Resistor - 0603; 0.063W; 1%")
      (fields (field (name "PART NUMBER") "10000044") (field (name "MANUFACTURER") "Multicomp"))
      (libsource (lib "HB_DB_Components") (part "Res"))
    )
    (comp (ref "R65")
      (value "100K")
      (footprint "RESC1608M")
      (description "Resistor - 0603; 0.063W; 1%")
      (fields (field (name "PART NUMBER") "10000045") (field (name "MANUFACTURER") "Multicomp"))
      (libsource (lib "HB_DB_Components") (part "Res"))
    )
    (comp (ref "R66")
      (value "4K7")
      (footprint "RESC1608M")
      (description "Resistor - 0603; 0.063W; 1%")
      (fields (field (name "PART NUMBER") "10000050") (field (name "MANUFACTURER") "Multicomp"))
      (libsource (lib "HB_DB_Components") (part "Res"))
    )
    (comp (ref "R67")
      (value "4K7")
      (footprint "RESC1608M")
      (description "Resistor - 0603; 0.063W; 1%")
      (fields (field (name "PART NUMBER") "10000050") (field (name "MANUFACTURER") "Multicomp"))
      (libsource (lib "HB_DB_Components") (part "Res"))
    )
    (comp (ref "R68")
      (value "100R")
      (footprint "RESC1608M")
      (description "Resistor - 0603; 0.063W; 1%")
      (fields (field (name "PART NUMBER") "10000042") (field (name "MANUFACTURER") "Multicomp"))
      (libsource (lib "HB_DB_Components") (part "Res"))
    )
    (comp (ref "R69")
      (value "100R")
      (footprint "RESC1608M")
      (description "Resistor - 0603; 0.063W; 1%")
      (fields (field (name "PART NUMBER") "10000042") (field (name "MANUFACTURER") "Multicomp"))
      (libsource (lib "HB_DB_Components") (part "Res"))
    )
    (comp (ref "R70")
      (value "10K")
      (footprint "RESC1608M")
      (description "Resistor - 0603; 0.063W; 1%")
      (fields (field (name "PART NUMBER") "10000044") (field (name "MANUFACTURER") "Multicomp"))
      (libsource (lib "HB_DB_Components") (part "Res"))
    )
    (comp (ref "R71")
      (value "10K")
      (footprint "RESC1608M")
      (description "Resistor - 0603; 0.063W; 1%")
      (fields (field (name "PART NUMBER") "10000044") (field (name "MANUFACTURER") "Multicomp"))
      (libsource (lib "HB_DB_Components") (part "Res"))
    )
    (comp (ref "R73")
      (value "6k8")
      (footprint "RESC2012L")
      (description "Resistor - 0805; 0.100W; 5%")
      (fields (field (name "PART NUMBER") "10000098"))
      (libsource (lib "HB_DB_Components") (part "Res"))
    )
    (comp (ref "R78")
      (value "6k8")
      (footprint "RESC2012L")
      (description "Resistor - 0805; 0.100W; 5%")
      (fields (field (name "PART NUMBER") "10000098"))
      (libsource (lib "HB_DB_Components") (part "Res"))
    )
    (comp (ref "R79")
      (value "6k8")
      (footprint "RESC2012L")
      (description "Resistor - 0805; 0.100W; 5%")
      (fields (field (name "PART NUMBER") "10000098"))
      (libsource (lib "HB_DB_Components") (part "Res"))
    )
    (comp (ref "R80")
      (value "6k8")
      (footprint "RESC2012L")
      (description "Resistor - 0805; 0.100W; 5%")
      (fields (field (name "PART NUMBER") "10000098"))
      (libsource (lib "HB_DB_Components") (part "Res"))
    )
    (comp (ref "R81")
      (value "6k8")
      (footprint "RESC2012L")
      (description "Resistor - 0805; 0.100W; 5%")
      (fields (field (name "PART NUMBER") "10000098"))
      (libsource (lib "HB_DB_Components") (part "Res"))
    )
    (comp (ref "R82")
      (value "6k8")
      (footprint "RESC2012L")
      (description "Resistor - 0805; 0.100W; 5%")
      (fields (field (name "PART NUMBER") "10000098"))
      (libsource (lib "HB_DB_Components") (part "Res"))
    )
    (comp (ref "R92")
      (value "10K")
      (footprint "RESC1608M")
      (description "Resistor - 0603; 0.063W; 1%")
      (fields (field (name "PART NUMBER") "10000044") (field (name "MANUFACTURER") "Multicomp"))
      (libsource (lib "HB_DB_Components") (part "Res"))
    )
    (comp (ref "R94")
      (value "10K")
      (footprint "RESC1608M")
      (description "Resistor - 0603; 0.063W; 1%")
      (fields (field (name "PART NUMBER") "10000044") (field (name "MANUFACTURER") "Multicomp"))
      (libsource (lib "HB_DB_Components") (part "Res"))
    )
    (comp (ref "R97")
      (value "10K")
      (footprint "RESC1608M")
      (description "Resistor - 0603; 0.063W; 1%")
      (fields (field (name "PART NUMBER") "10000044") (field (name "MANUFACTURER") "Multicomp"))
      (libsource (lib "HB_DB_Components") (part "Res"))
    )
    (comp (ref "R104")
      (value "10K")
      (footprint "RESC1608M")
      (description "Resistor - 0603; 0.063W; 1%")
      (fields (field (name "PART NUMBER") "10000044") (field (name "MANUFACTURER") "Multicomp"))
      (libsource (lib "HB_DB_Components") (part "Res"))
    )
    (comp (ref "R106")
      (value "1K5")
      (footprint "RESC1608M")
      (description "Resistor - 0603; 0.063W; 1%")
      (fields (field (name "PART NUMBER") "10000048") (field (name "MANUFACTURER") "Multicomp"))
      (libsource (lib "HB_DB_Components") (part "Res"))
    )
    (comp (ref "R107")
      (value "100R")
      (footprint "RESC1608M")
      (description "Resistor - 0603; 0.063W; 1%")
      (fields (field (name "PART NUMBER") "10000042") (field (name "MANUFACTURER") "Multicomp"))
      (libsource (lib "HB_DB_Components") (part "Res"))
    )
    (comp (ref "R108")
      (value "6k8")
      (footprint "RESC2012L")
      (description "Resistor - 0805; 0.100W; 5%")
      (fields (field (name "PART NUMBER") "10000098"))
      (libsource (lib "HB_DB_Components") (part "Res"))
    )
    (comp (ref "R109")
      (value "6k8")
      (footprint "RESC2012L")
      (description "Resistor - 0805; 0.100W; 5%")
      (fields (field (name "PART NUMBER") "10000098"))
      (libsource (lib "HB_DB_Components") (part "Res"))
    )
    (comp (ref "R110")
      (value "6k8")
      (footprint "RESC2012L")
      (description "Resistor - 0805; 0.100W; 5%")
      (fields (field (name "PART NUMBER") "10000098"))
      (libsource (lib "HB_DB_Components") (part "Res"))
    )
    (comp (ref "R111")
      (value "6k8")
      (footprint "RESC2012L")
      (description "Resistor - 0805; 0.100W; 5%")
      (fields (field (name "PART NUMBER") "10000098"))
      (libsource (lib "HB_DB_Components") (part "Res"))
    )
    (comp (ref "R112")
      (value "6k8")
      (footprint "RESC2012L")
      (description "Resistor - 0805; 0.100W; 5%")
      (fields (field (name "PART NUMBER") "10000098"))
      (libsource (lib "HB_DB_Components") (part "Res"))
    )
    (comp (ref "R113")
      (value "6k8")
      (footprint "RESC2012L")
      (description "Resistor - 0805; 0.100W; 5%")
      (fields (field (name "PART NUMBER") "10000098"))
      (libsource (lib "HB_DB_Components") (part "Res"))
    )
    (comp (ref "R114")
      (value "6k8")
      (footprint "RESC2012L")
      (description "Resistor - 0805; 0.100W; 5%")
      (fields (field (name "PART NUMBER") "10000098"))
      (libsource (lib "HB_DB_Components") (part "Res"))
    )
    (comp (ref "U1")
      (value "A4988")
      (footprint "QFN50P500X500X100-28M")
      (description "A4988 (A4983 pinout compatible)")
      (fields (field (name "PART NUMBER") "10000094") (field (name "MANUFACTURER") "Allegro"))
      (libsource (lib "HB_DB_Components") (part "IC A4988"))
    )
    (comp (ref "U2")
      (value "A4988")
      (footprint "QFN50P500X500X100-28M")
      (description "A4988 (A4983 pinout compatible)")
      (fields (field (name "PART NUMBER") "10000094") (field (name "MANUFACTURER") "Allegro"))
      (libsource (lib "HB_DB_Components") (part "IC A4988"))
    )
    (comp (ref "U3")
      (value "A4988")
      (footprint "QFN50P500X500X100-28M")
      (description "A4988 (A4983 pinout compatible)")
      (fields (field (name "PART NUMBER") "10000094") (field (name "MANUFACTURER") "Allegro"))
      (libsource (lib "HB_DB_Components") (part "IC A4988"))
    )
    (comp (ref "U4")
      (value "A4988")
      (footprint "QFN50P500X500X100-28M")
      (description "A4988 (A4983 pinout compatible)")
      (fields (field (name "PART NUMBER") "10000094") (field (name "MANUFACTURER") "Allegro"))
      (libsource (lib "HB_DB_Components") (part "IC A4988"))
    )
  )
  (nets
    (net (code "1") (name "/CTC1_Heat") (class "Default")
      (node (ref "R69") (pin "1") (pinfunction "1_1") (pintype "passive"))
      (node (ref "R92") (pin "2") (pinfunction "2_2") (pintype "passive"))
    )
    (net (code "2") (name "/CTC1_NTC1") (class "Default")
      (node (ref "J8") (pin "1") (pinfunction "1_1") (pintype "passive"))
      (node (ref "L2") (pin "2") (pinfunction "2_2") (pintype "passive"))
    )
    (net (code "3") (name "/CTC1_NTC2") (class "Default")
      (node (ref "J8") (pin "2") (pinfunction "2_2") (pintype "passive"))
      (node (ref "L4") (pin "2") (pinfunction "2_2") (pintype "passive"))
    )
    (net (code "4") (name "/CTC1_Temp") (class "Default")
      (node (ref "C39") (pin "2") (pinfunction "2_2") (pintype "passive"))
      (node (ref "C40") (pin "2") (pinfunction "2_2") (pintype "passive"))
      (node (ref "L2") (pin "1") (pinfunction "1_1") (pintype "passive"))
      (node (ref "R60") (pin "1") (pinfunction "1_1") (pintype "passive"))
    )
    (net (code "5") (name "/CTC2_Heat") (class "Default")
      (node (ref "R68") (pin "1") (pinfunction "1_1") (pintype "passive"))
      (node (ref "R70") (pin "2") (pinfunction "2_2") (pintype "passive"))
    )
    (net (code "6") (name "/CTC2_NTC1") (class "Default")
      (node (ref "J7") (pin "1") (pinfunction "1_1") (pintype "passive"))
      (node (ref "L1") (pin "2") (pinfunction "2_2") (pintype "passive"))
    )
    (net (code "7") (name "/CTC2_NTC2") (class "Default")
      (node (ref "J7") (pin "2") (pinfunction "2_2") (pintype "passive"))
      (node (ref "L3") (pin "2") (pinfunction "2_2") (pintype "passive"))
    )
    (net (code "8") (name "/CTC2_Temp") (class "Default")
      (node (ref "C37") (pin "2") (pinfunction "2_2") (pintype "passive"))
      (node (ref "C38") (pin "2") (pinfunction "2_2") (pintype "passive"))
      (node (ref "L1") (pin "1") (pinfunction "1_1") (pintype "passive"))
      (node (ref "R59") (pin "1") (pinfunction "1_1") (pintype "passive"))
    )
    (net (code "9") (name "/E1_Motor_1A") (class "Default")
      (node (ref "J5") (pin "2") (pinfunction "2_2") (pintype "passive"))
      (node (ref "R110") (pin "1") (pinfunction "1_1") (pintype "passive"))
      (node (ref "U4") (pin "24") (pinfunction "OUT1A_24") (pintype "passive"))
    )
    (net (code "10") (name "/E1_Motor_1B") (class "Default")
      (node (ref "J5") (pin "1") (pinfunction "1_1") (pintype "passive"))
      (node (ref "R108") (pin "1") (pinfunction "1_1") (pintype "passive"))
      (node (ref "U4") (pin "21") (pinfunction "OUT1B_21") (pintype "passive"))
    )
    (net (code "11") (name "/E1_Motor_2A") (class "Default")
      (node (ref "J5") (pin "3") (pinfunction "3_3") (pintype "passive"))
      (node (ref "R112") (pin "1") (pinfunction "1_1") (pintype "passive"))
      (node (ref "U4") (pin "26") (pinfunction "OUT2A_26") (pintype "passive"))
    )
    (net (code "12") (name "/E1_Motor_2B") (class "Default")
      (node (ref "J5") (pin "4") (pinfunction "4_4") (pintype "passive"))
      (node (ref "R114") (pin "1") (pinfunction "1_1") (pintype "passive"))
      (node (ref "U4") (pin "1") (pinfunction "OUT2B_1") (pintype "passive"))
    )
    (net (code "13") (name "/ME_DIR") (class "Default")
      (node (ref "J15") (pin "4") (pinfunction "4_4") (pintype "passive"))
      (node (ref "U4") (pin "19") (pinfunction "DIR_19") (pintype "input"))
    )
    (net (code "14") (name "/ME_EN") (class "Default")
      (node (ref "J15") (pin "3") (pinfunction "3_3") (pintype "passive"))
      (node (ref "U4") (pin "2") (pinfunction "ENABLE_2") (pintype "passive"))
    )
    (net (code "15") (name "/ME_STEP") (class "Default")
      (node (ref "J15") (pin "5") (pinfunction "5_5") (pintype "passive"))
      (node (ref "R54") (pin "2") (pinfunction "2_2") (pintype "passive"))
      (node (ref "U4") (pin "16") (pinfunction "STEP_16") (pintype "input"))
    )
    (net (code "16") (name "/MX_DIR") (class "Default")
      (node (ref "J12") (pin "4") (pinfunction "4_4") (pintype "passive"))
      (node (ref "U1") (pin "19") (pinfunction "DIR_19") (pintype "input"))
    )
    (net (code "17") (name "/MX_EN") (class "Default")
      (node (ref "J12") (pin "3") (pinfunction "3_3") (pintype "passive"))
      (node (ref "U1") (pin "2") (pinfunction "ENABLE_2") (pintype "passive"))
    )
    (net (code "18") (name "/MX_STEP") (class "Default")
      (node (ref "J12") (pin "5") (pinfunction "5_5") (pintype "passive"))
      (node (ref "R24") (pin "2") (pinfunction "2_2") (pintype "passive"))
      (node (ref "U1") (pin "16") (pinfunction "STEP_16") (pintype "input"))
    )
    (net (code "19") (name "/MY_DIR") (class "Default")
      (node (ref "J13") (pin "4") (pinfunction "4_4") (pintype "passive"))
      (node (ref "U2") (pin "19") (pinfunction "DIR_19") (pintype "input"))
    )
    (net (code "20") (name "/MY_EN") (class "Default")
      (node (ref "J13") (pin "3") (pinfunction "3_3") (pintype "passive"))
      (node (ref "U2") (pin "2") (pinfunction "ENABLE_2") (pintype "passive"))
    )
    (net (code "21") (name "/MY_STEP") (class "Default")
      (node (ref "J13") (pin "5") (pinfunction "5_5") (pintype "passive"))
      (node (ref "R25") (pin "2") (pinfunction "2_2") (pintype "passive"))
      (node (ref "U2") (pin "16") (pinfunction "STEP_16") (pintype "input"))
    )
    (net (code "22") (name "/MZ_DIR") (class "Default")
      (node (ref "J14") (pin "4") (pinfunction "4_4") (pintype "passive"))
      (node (ref "U3") (pin "19") (pinfunction "DIR_19") (pintype "input"))
    )
    (net (code "23") (name "/MZ_EN") (class "Default")
      (node (ref "J14") (pin "3") (pinfunction "3_3") (pintype "passive"))
      (node (ref "U3") (pin "2") (pinfunction "ENABLE_2") (pintype "passive"))
    )
    (net (code "24") (name "/MZ_STEP") (class "Default")
      (node (ref "J14") (pin "5") (pinfunction "5_5") (pintype "passive"))
      (node (ref "R53") (pin "2") (pinfunction "2_2") (pintype "passive"))
      (node (ref "U3") (pin "16") (pinfunction "STEP_16") (pintype "input"))
    )
    (net (code "25") (name "/Mn_RST") (class "Default")
      (node (ref "J12") (pin "2") (pinfunction "2_2") (pintype "passive"))
      (node (ref "J13") (pin "2") (pinfunction "2_2") (pintype "passive"))
      (node (ref "J14") (pin "2") (pinfunction "2_2") (pintype "passive"))
      (node (ref "J15") (pin "2") (pinfunction "2_2") (pintype "passive"))
      (node (ref "U1") (pin "12") (pinfunction "RESET_12") (pintype "passive"))
      (node (ref "U2") (pin "12") (pinfunction "RESET_12") (pintype "passive"))
      (node (ref "U3") (pin "12") (pinfunction "RESET_12") (pintype "passive"))
      (node (ref "U4") (pin "12") (pinfunction "RESET_12") (pintype "passive"))
    )
    (net (code "26") (name "/Opto_X_IN") (class "Default")
      (node (ref "C71") (pin "1") (pinfunction "1_1") (pintype "passive"))
      (node (ref "D1") (pin "1") (pinfunction "K_1") (pintype "passive"))
      (node (ref "D21") (pin "2") (pinfunction "A_2") (pintype "passive"))
      (node (ref "R64") (pin "1") (pinfunction "1_1") (pintype "passive"))
    )
    (net (code "27") (name "/Opto_Y_IN") (class "Default")
      (node (ref "C72") (pin "1") (pinfunction "1_1") (pintype "passive"))
      (node (ref "D22") (pin "2") (pinfunction "A_2") (pintype "passive"))
      (node (ref "D4") (pin "1") (pinfunction "K_1") (pintype "passive"))
      (node (ref "R97") (pin "1") (pinfunction "1_1") (pintype "passive"))
    )
    (net (code "28") (name "/Opto_Z_IN") (class "Default")
      (node (ref "C73") (pin "1") (pinfunction "1_1") (pintype "passive"))
      (node (ref "D23") (pin "2") (pinfunction "A_2") (pintype "passive"))
      (node (ref "D7") (pin "1") (pinfunction "K_1") (pintype "passive"))
      (node (ref "R104") (pin "1") (pinfunction "1_1") (pintype "passive"))
    )
    (net (code "29") (name "/Thermocouple") (class "Default")
      (node (ref "C69") (pin "2") (pinfunction "2_2") (pintype "passive"))
      (node (ref "L10") (pin "1") (pinfunction "1_1") (pintype "passive"))
    )
    (net (code "30") (name "/X_Motor_1A") (class "Default")
      (node (ref "J1") (pin "2") (pinfunction "2_2") (pintype "passive"))
      (node (ref "R40") (pin "1") (pinfunction "1_1") (pintype "passive"))
      (node (ref "U1") (pin "24") (pinfunction "OUT1A_24") (pintype "passive"))
    )
    (net (code "31") (name "/X_Motor_1B") (class "Default")
      (node (ref "J1") (pin "1") (pinfunction "1_1") (pintype "passive"))
      (node (ref "R34") (pin "1") (pinfunction "1_1") (pintype "passive"))
      (node (ref "U1") (pin "21") (pinfunction "OUT1B_21") (pintype "passive"))
    )
    (net (code "32") (name "/X_Motor_2A") (class "Default")
      (node (ref "J1") (pin "3") (pinfunction "3_3") (pintype "passive"))
      (node (ref "R78") (pin "1") (pinfunction "1_1") (pintype "passive"))
      (node (ref "U1") (pin "26") (pinfunction "OUT2A_26") (pintype "passive"))
    )
    (net (code "33") (name "/X_Motor_2B") (class "Default")
      (node (ref "J1") (pin "4") (pinfunction "4_4") (pintype "passive"))
      (node (ref "R80") (pin "1") (pinfunction "1_1") (pintype "passive"))
      (node (ref "U1") (pin "1") (pinfunction "OUT2B_1") (pintype "passive"))
    )
    (net (code "34") (name "/Y_Motor_1A") (class "Default")
      (node (ref "J2") (pin "2") (pinfunction "2_2") (pintype "passive"))
      (node (ref "R73") (pin "1") (pinfunction "1_1") (pintype "passive"))
      (node (ref "U2") (pin "24") (pinfunction "OUT1A_24") (pintype "passive"))
    )
    (net (code "35") (name "/Y_Motor_1B") (class "Default")
      (node (ref "J2") (pin "1") (pinfunction "1_1") (pintype "passive"))
      (node (ref "R39") (pin "1") (pinfunction "1_1") (pintype "passive"))
      (node (ref "U2") (pin "21") (pinfunction "OUT1B_21") (pintype "passive"))
    )
    (net (code "36") (name "/Y_Motor_2A") (class "Default")
      (node (ref "J2") (pin "3") (pinfunction "3_3") (pintype "passive"))
      (node (ref "R79") (pin "1") (pinfunction "1_1") (pintype "passive"))
      (node (ref "U2") (pin "26") (pinfunction "OUT2A_26") (pintype "passive"))
    )
    (net (code "37") (name "/Y_Motor_2B") (class "Default")
      (node (ref "J2") (pin "4") (pinfunction "4_4") (pintype "passive"))
      (node (ref "R81") (pin "1") (pinfunction "1_1") (pintype "passive"))
      (node (ref "U2") (pin "1") (pinfunction "OUT2B_1") (pintype "passive"))
    )
    (net (code "38") (name "/Z_Motor_1A") (class "Default")
      (node (ref "J4") (pin "2") (pinfunction "2_2") (pintype "passive"))
      (node (ref "R109") (pin "1") (pinfunction "1_1") (pintype "passive"))
      (node (ref "U3") (pin "24") (pinfunction "OUT1A_24") (pintype "passive"))
    )
    (net (code "39") (name "/Z_Motor_1B") (class "Default")
      (node (ref "J4") (pin "1") (pinfunction "1_1") (pintype "passive"))
      (node (ref "R82") (pin "1") (pinfunction "1_1") (pintype "passive"))
      (node (ref "U3") (pin "21") (pinfunction "OUT1B_21") (pintype "passive"))
    )
    (net (code "40") (name "/Z_Motor_2A") (class "Default")
      (node (ref "J4") (pin "3") (pinfunction "3_3") (pintype "passive"))
      (node (ref "R111") (pin "1") (pinfunction "1_1") (pintype "passive"))
      (node (ref "U3") (pin "26") (pinfunction "OUT2A_26") (pintype "passive"))
    )
    (net (code "41") (name "/Z_Motor_2B") (class "Default")
      (node (ref "J4") (pin "4") (pinfunction "4_4") (pintype "passive"))
      (node (ref "R113") (pin "1") (pinfunction "1_1") (pintype "passive"))
      (node (ref "U3") (pin "1") (pinfunction "OUT2B_1") (pintype "passive"))
    )
    (net (code "42") (name "GND") (class "Default")
      (node (ref "C10") (pin "1") (pinfunction "1_1") (pintype "passive"))
      (node (ref "C11") (pin "2") (pinfunction "2_2") (pintype "passive"))
      (node (ref "C12") (pin "2") (pinfunction "2_2") (pintype "passive"))
      (node (ref "C15") (pin "1") (pinfunction "1_1") (pintype "passive"))
      (node (ref "C16") (pin "1") (pinfunction "1_1") (pintype "passive"))
      (node (ref "C17") (pin "1") (pinfunction "1_1") (pintype "passive"))
      (node (ref "C18") (pin "2") (pinfunction "2_2") (pintype "passive"))
      (node (ref "C21") (pin "1") (pinfunction "1_1") (pintype "passive"))
      (node (ref "C22") (pin "1") (pinfunction "1_1") (pintype "passive"))
      (node (ref "C23") (pin "1") (pinfunction "1_1") (pintype "passive"))
      (node (ref "C24") (pin "1") (pinfunction "1_1") (pintype "passive"))
      (node (ref "C25") (pin "1") (pinfunction "1_1") (pintype "passive"))
      (node (ref "C26") (pin "1") (pinfunction "1_1") (pintype "passive"))
      (node (ref "C27") (pin "2") (pinfunction "2_2") (pintype "passive"))
      (node (ref "C28") (pin "1") (pinfunction "1_1") (pintype "passive"))
      (node (ref "C29") (pin "1") (pinfunction "1_1") (pintype "passive"))
      (node (ref "C3") (pin "1") (pinfunction "1_1") (pintype "passive"))
      (node (ref "C31") (pin "2") (pinfunction "2_2") (pintype "passive"))
      (node (ref "C33") (pin "1") (pinfunction "1_1") (pintype "passive"))
      (node (ref "C34") (pin "1") (pinfunction "1_1") (pintype "passive"))
      (node (ref "C35") (pin "1") (pinfunction "1_1") (pintype "passive"))
      (node (ref "C36") (pin "1") (pinfunction "1_1") (pintype "passive"))
      (node (ref "C4") (pin "1") (pinfunction "1_1") (pintype "passive"))
      (node (ref "C5") (pin "1") (pinfunction "1_1") (pintype "passive"))
      (node (ref "C6") (pin "1") (pinfunction "1_1") (pintype "passive"))
      (node (ref "C62") (pin "1") (pinfunction "1_1") (pintype "passive"))
      (node (ref "C7") (pin "2") (pinfunction "2_2") (pintype "passive"))
      (node (ref "C71") (pin "2") (pinfunction "2_2") (pintype "passive"))
      (node (ref "C72") (pin "2") (pinfunction "2_2") (pintype "passive"))
      (node (ref "C73") (pin "2") (pinfunction "2_2") (pintype "passive"))
      (node (ref "C8") (pin "1") (pinfunction "1_1") (pintype "passive"))
      (node (ref "C9") (pin "1") (pinfunction "1_1") (pintype "passive"))
      (node (ref "D17") (pin "2") (pinfunction "A_2") (pintype "passive"))
      (node (ref "D18") (pin "2") (pinfunction "A_2") (pintype "passive"))
      (node (ref "J12") (pin "6") (pinfunction "6_6") (pintype "passive"))
      (node (ref "J13") (pin "6") (pinfunction "6_6") (pintype "passive"))
      (node (ref "J14") (pin "6") (pinfunction "6_6") (pintype "passive"))
      (node (ref "J15") (pin "6") (pinfunction "6_6") (pintype "passive"))
      (node (ref "J21") (pin "2") (pinfunction "2_2") (pintype "passive"))
      (node (ref "J3") (pin "5") (pinfunction "5_5") (pintype "passive"))
      (node (ref "J3") (pin "6") (pinfunction "6_6") (pintype "passive"))
      (node (ref "J6") (pin "5") (pinfunction "5_5") (pintype "passive"))
      (node (ref "J6") (pin "6") (pinfunction "6_6") (pintype "passive"))
      (node (ref "J9") (pin "5") (pinfunction "5_5") (pintype "passive"))
      (node (ref "J9") (pin "6") (pinfunction "6_6") (pintype "passive"))
      (node (ref "P1") (pin "1") (pinfunction "TOP_1") (pintype "passive"))
      (node (ref "P2") (pin "1") (pinfunction "TOP_1") (pintype "passive"))
      (node (ref "P3") (pin "1") (pinfunction "TOP_1") (pintype "passive"))
      (node (ref "P4") (pin "1") (pinfunction "TOP_1") (pintype "passive"))
      (node (ref "Q1") (pin "2") (pinfunction "S_2") (pintype "passive"))
      (node (ref "Q10") (pin "2") (pinfunction "S_2") (pintype "passive"))
      (node (ref "Q12") (pin "2") (pinfunction "S_2") (pintype "passive"))
      (node (ref "Q2") (pin "2") (pinfunction "S_2") (pintype "passive"))
      (node (ref "Q3") (pin "2") (pinfunction "S_2") (pintype "passive"))
      (node (ref "Q4") (pin "2") (pinfunction "S_2") (pintype "passive"))
      (node (ref "Q5") (pin "3") (pinfunction "S_3") (pintype "passive"))
      (node (ref "Q6") (pin "3") (pinfunction "S_3") (pintype "passive"))
      (node (ref "R108") (pin "2") (pinfunction "2_2") (pintype "passive"))
      (node (ref "R109") (pin "2") (pinfunction "2_2") (pintype "passive"))
      (node (ref "R110") (pin "2") (pinfunction "2_2") (pintype "passive"))
      (node (ref "R111") (pin "2") (pinfunction "2_2") (pintype "passive"))
      (node (ref "R112") (pin "2") (pinfunction "2_2") (pintype "passive"))
      (node (ref "R113") (pin "2") (pinfunction "2_2") (pintype "passive"))
      (node (ref "R114") (pin "2") (pinfunction "2_2") (pintype "passive"))
      (node (ref "R20") (pin "1") (pinfunction "1_1") (pintype "passive"))
      (node (ref "R21") (pin "1") (pinfunction "1_1") (pintype "passive"))
      (node (ref "R22") (pin "1") (pinfunction "1_1") (pintype "passive"))
      (node (ref "R23") (pin "1") (pinfunction "1_1") (pintype "passive"))
      (node (ref "R26") (pin "1") (pinfunction "1_1") (pintype "passive"))
      (node (ref "R27") (pin "1") (pinfunction "1_1") (pintype "passive"))
      (node (ref "R28") (pin "1") (pinfunction "1_1") (pintype "passive"))
      (node (ref "R29") (pin "1") (pinfunction "1_1") (pintype "passive"))
      (node (ref "R34") (pin "2") (pinfunction "2_2") (pintype "passive"))
      (node (ref "R39") (pin "2") (pinfunction "2_2") (pintype "passive"))
      (node (ref "R40") (pin "2") (pinfunction "2_2") (pintype "passive"))
      (node (ref "R49") (pin "1") (pinfunction "1_1") (pintype "passive"))
      (node (ref "R50") (pin "1") (pinfunction "1_1") (pintype "passive"))
      (node (ref "R51") (pin "1") (pinfunction "1_1") (pintype "passive"))
      (node (ref "R52") (pin "1") (pinfunction "1_1") (pintype "passive"))
      (node (ref "R55") (pin "1") (pinfunction "1_1") (pintype "passive"))
      (node (ref "R56") (pin "1") (pinfunction "1_1") (pintype "passive"))
      (node (ref "R57") (pin "1") (pinfunction "1_1") (pintype "passive"))
      (node (ref "R58") (pin "1") (pinfunction "1_1") (pintype "passive"))
      (node (ref "R70") (pin "1") (pinfunction "1_1") (pintype "passive"))
      (node (ref "R71") (pin "1") (pinfunction "1_1") (pintype "passive"))
      (node (ref "R73") (pin "2") (pinfunction "2_2") (pintype "passive"))
      (node (ref "R78") (pin "2") (pinfunction "2_2") (pintype "passive"))
      (node (ref "R79") (pin "2") (pinfunction "2_2") (pintype "passive"))
      (node (ref "R80") (pin "2") (pinfunction "2_2") (pintype "passive"))
      (node (ref "R81") (pin "2") (pinfunction "2_2") (pintype "passive"))
      (node (ref "R82") (pin "2") (pinfunction "2_2") (pintype "passive"))
      (node (ref "R92") (pin "1") (pinfunction "1_1") (pintype "passive"))
      (node (ref "R94") (pin "1") (pinfunction "1_1") (pintype "passive"))
      (node (ref "U1") (pin "18") (pinfunction "GND_18") (pintype "passive"))
      (node (ref "U1") (pin "29") (pinfunction "PAD_29") (pintype "passive"))
      (node (ref "U1") (pin "3") (pinfunction "GND_3") (pintype "passive"))
      (node (ref "U2") (pin "18") (pinfunction "GND_18") (pintype "passive"))
      (node (ref "U2") (pin "29") (pinfunction "PAD_29") (pintype "passive"))
      (node (ref "U2") (pin "3") (pinfunction "GND_3") (pintype "passive"))
      (node (ref "U3") (pin "18") (pinfunction "GND_18") (pintype "passive"))
      (node (ref "U3") (pin "29") (pinfunction "PAD_29") (pintype "passive"))
      (node (ref "U3") (pin "3") (pinfunction "GND_3") (pintype "passive"))
      (node (ref "U4") (pin "18") (pinfunction "GND_18") (pintype "passive"))
      (node (ref "U4") (pin "29") (pinfunction "PAD_29") (pintype "passive"))
      (node (ref "U4") (pin "3") (pinfunction "GND_3") (pintype "passive"))
    )
    (net (code "43") (name "GND_A") (class "Default")
      (node (ref "C37") (pin "1") (pinfunction "1_1") (pintype "passive"))
      (node (ref "C38") (pin "1") (pinfunction "1_1") (pintype "passive"))
      (node (ref "C39") (pin "1") (pinfunction "1_1") (pintype "passive"))
      (node (ref "C40") (pin "1") (pinfunction "1_1") (pintype "passive"))
      (node (ref "C69") (pin "1") (pinfunction "1_1") (pintype "passive"))
      (node (ref "L11") (pin "1") (pinfunction "1_1") (pintype "passive"))
      (node (ref "L3") (pin "1") (pinfunction "1_1") (pintype "passive"))
      (node (ref "L4") (pin "1") (pinfunction "1_1") (pintype "passive"))
    )
    (net (code "44") (name "Net-(D1-A)") (class "Default")
      (node (ref "D1") (pin "2") (pinfunction "A_2") (pintype "passive"))
      (node (ref "R13") (pin "1") (pinfunction "1_1") (pintype "passive"))
    )
    (net (code "45") (name "Net-(D2-K)") (class "Default")
      (node (ref "D2") (pin "1") (pinfunction "K_1") (pintype "passive"))
      (node (ref "R16") (pin "2") (pinfunction "2_2") (pintype "passive"))
    )
    (net (code "46") (name "Net-(D3-K)") (class "Default")
      (node (ref "D3") (pin "1") (pinfunction "K_1") (pintype "passive"))
      (node (ref "R17") (pin "2") (pinfunction "2_2") (pintype "passive"))
    )
    (net (code "47") (name "Net-(D4-A)") (class "Default")
      (node (ref "D4") (pin "2") (pinfunction "A_2") (pintype "passive"))
      (node (ref "R42") (pin "1") (pinfunction "1_1") (pintype "passive"))
    )
    (net (code "48") (name "Net-(D5-K)") (class "Default")
      (node (ref "D5") (pin "1") (pinfunction "K_1") (pintype "passive"))
      (node (ref "R46") (pin "2") (pinfunction "2_2") (pintype "passive"))
    )
    (net (code "49") (name "Net-(D6-K)") (class "Default")
      (node (ref "D6") (pin "1") (pinfunction "K_1") (pintype "passive"))
      (node (ref "R61") (pin "2") (pinfunction "2_2") (pintype "passive"))
    )
    (net (code "50") (name "Net-(D7-A)") (class "Default")
      (node (ref "D7") (pin "2") (pinfunction "A_2") (pintype "passive"))
      (node (ref "R45") (pin "1") (pinfunction "1_1") (pintype "passive"))
    )
    (net (code "51") (name "Net-(D8-A)") (class "Default")
      (node (ref "D8") (pin "2") (pinfunction "A_2") (pintype "passive"))
      (node (ref "R66") (pin "1") (pinfunction "1_1") (pintype "passive"))
    )
    (net (code "52") (name "Net-(D9-A)") (class "Default")
      (node (ref "D9") (pin "2") (pinfunction "A_2") (pintype "passive"))
      (node (ref "R67") (pin "1") (pinfunction "1_1") (pintype "passive"))
    )
    (net (code "53") (name "Net-(D15-A)") (class "Default")
      (node (ref "D15") (pin "2") (pinfunction "A_2") (pintype "passive"))
      (node (ref "D9") (pin "1") (pinfunction "K_1") (pintype "passive"))
      (node (ref "J8") (pin "4") (pinfunction "4_4") (pintype "passive"))
      (node (ref "Q5") (pin "2") (pinfunction "D_2") (pintype "passive"))
    )
    (net (code "54") (name "Net-(D16-A)") (class "Default")
      (node (ref "D16") (pin "2") (pinfunction "A_2") (pintype "passive"))
      (node (ref "D8") (pin "1") (pinfunction "K_1") (pintype "passive"))
      (node (ref "J7") (pin "4") (pinfunction "4_4") (pintype "passive"))
      (node (ref "Q6") (pin "2") (pinfunction "D_2") (pintype "passive"))
    )
    (net (code "55") (name "Net-(D17-K)") (class "Default")
      (node (ref "D17") (pin "1") (pinfunction "K_1") (pintype "passive"))
      (node (ref "Q9") (pin "2") (pinfunction "S_2") (pintype "passive"))
      (node (ref "R43") (pin "1") (pinfunction "1_1") (pintype "passive"))
      (node (ref "R65") (pin "2") (pinfunction "2_2") (pintype "passive"))
    )
    (net (code "56") (name "Net-(D18-K)") (class "Default")
      (node (ref "D18") (pin "1") (pinfunction "K_1") (pintype "passive"))
      (node (ref "Q11") (pin "2") (pinfunction "S_2") (pintype "passive"))
      (node (ref "R106") (pin "1") (pinfunction "1_1") (pintype "passive"))
      (node (ref "R63") (pin "2") (pinfunction "2_2") (pintype "passive"))
    )
    (net (code "57") (name "Net-(D21-K)") (class "Default")
      (node (ref "D21") (pin "1") (pinfunction "K_1") (pintype "passive"))
      (node (ref "J3") (pin "3") (pinfunction "3_3") (pintype "passive"))
      (node (ref "J3") (pin "4") (pinfunction "4_4") (pintype "passive"))
    )
    (net (code "58") (name "Net-(D22-K)") (class "Default")
      (node (ref "D22") (pin "1") (pinfunction "K_1") (pintype "passive"))
      (node (ref "J6") (pin "3") (pinfunction "3_3") (pintype "passive"))
      (node (ref "J6") (pin "4") (pinfunction "4_4") (pintype "passive"))
    )
    (net (code "59") (name "Net-(D23-K)") (class "Default")
      (node (ref "D23") (pin "1") (pinfunction "K_1") (pintype "passive"))
      (node (ref "J9") (pin "3") (pinfunction "3_3") (pintype "passive"))
      (node (ref "J9") (pin "4") (pinfunction "4_4") (pintype "passive"))
    )
    (net (code "60") (name "Net-(J17-Pad1)") (class "Default")
      (node (ref "J17") (pin "1") (pinfunction "1_1") (pintype "passive"))
      (node (ref "L11") (pin "2") (pinfunction "2_2") (pintype "passive"))
      (node (ref "R10") (pin "2") (pinfunction "2_2") (pintype "passive"))
    )
    (net (code "61") (name "Net-(J17-Pad3)") (class "Default")
      (node (ref "J17") (pin "3") (pinfunction "3_3") (pintype "passive"))
      (node (ref "R5") (pin "2") (pinfunction "2_2") (pintype "passive"))
    )
    (net (code "62") (name "Net-(L10-Pad2)") (class "Default")
      (node (ref "L10") (pin "2") (pinfunction "2_2") (pintype "passive"))
      (node (ref "R10") (pin "1") (pinfunction "1_1") (pintype "passive"))
      (node (ref "R5") (pin "1") (pinfunction "1_1") (pintype "passive"))
    )
    (net (code "63") (name "Net-(P1-BOT)") (class "Default")
      (node (ref "C17") (pin "2") (pinfunction "2_2") (pintype "passive"))
      (node (ref "P1") (pin "3") (pinfunction "BOT_3") (pintype "passive"))
      (node (ref "R18") (pin "1") (pinfunction "1_1") (pintype "passive"))
    )
    (net (code "64") (name "Net-(P1-TAP)") (class "Default")
      (node (ref "P1") (pin "2") (pinfunction "TAP_2") (pintype "passive"))
      (node (ref "U1") (pin "17") (pinfunction "REF_17") (pintype "passive"))
    )
    (net (code "65") (name "Net-(P2-BOT)") (class "Default")
      (node (ref "C18") (pin "1") (pinfunction "1_1") (pintype "passive"))
      (node (ref "P2") (pin "3") (pinfunction "BOT_3") (pintype "passive"))
      (node (ref "R19") (pin "1") (pinfunction "1_1") (pintype "passive"))
    )
    (net (code "66") (name "Net-(P2-TAP)") (class "Default")
      (node (ref "P2") (pin "2") (pinfunction "TAP_2") (pintype "passive"))
      (node (ref "U2") (pin "17") (pinfunction "REF_17") (pintype "passive"))
    )
    (net (code "67") (name "Net-(P3-BOT)") (class "Default")
      (node (ref "C35") (pin "2") (pinfunction "2_2") (pintype "passive"))
      (node (ref "P3") (pin "3") (pinfunction "BOT_3") (pintype "passive"))
      (node (ref "R47") (pin "1") (pinfunction "1_1") (pintype "passive"))
    )
    (net (code "68") (name "Net-(P3-TAP)") (class "Default")
      (node (ref "P3") (pin "2") (pinfunction "TAP_2") (pintype "passive"))
      (node (ref "U3") (pin "17") (pinfunction "REF_17") (pintype "passive"))
    )
    (net (code "69") (name "Net-(P4-BOT)") (class "Default")
      (node (ref "C36") (pin "2") (pinfunction "2_2") (pintype "passive"))
      (node (ref "P4") (pin "3") (pinfunction "BOT_3") (pintype "passive"))
      (node (ref "R48") (pin "1") (pinfunction "1_1") (pintype "passive"))
    )
    (net (code "70") (name "Net-(P4-TAP)") (class "Default")
      (node (ref "P4") (pin "2") (pinfunction "TAP_2") (pintype "passive"))
      (node (ref "U4") (pin "17") (pinfunction "REF_17") (pintype "passive"))
    )
    (net (code "71") (name "Net-(Q1-D)") (class "Default")
      (node (ref "Q1") (pin "3") (pinfunction "D_3") (pintype "passive"))
      (node (ref "R16") (pin "1") (pinfunction "1_1") (pintype "passive"))
    )
    (net (code "72") (name "Net-(Q1-G)") (class "Default")
      (node (ref "Q1") (pin "1") (pinfunction "G_1") (pintype "passive"))
      (node (ref "R24") (pin "1") (pinfunction "1_1") (pintype "passive"))
    )
    (net (code "73") (name "Net-(Q2-D)") (class "Default")
      (node (ref "Q2") (pin "3") (pinfunction "D_3") (pintype "passive"))
      (node (ref "R17") (pin "1") (pinfunction "1_1") (pintype "passive"))
    )
    (net (code "74") (name "Net-(Q2-G)") (class "Default")
      (node (ref "Q2") (pin "1") (pinfunction "G_1") (pintype "passive"))
      (node (ref "R25") (pin "1") (pinfunction "1_1") (pintype "passive"))
    )
    (net (code "75") (name "Net-(Q3-D)") (class "Default")
      (node (ref "Q3") (pin "3") (pinfunction "D_3") (pintype "passive"))
      (node (ref "R46") (pin "1") (pinfunction "1_1") (pintype "passive"))
    )
    (net (code "76") (name "Net-(Q3-G)") (class "Default")
      (node (ref "Q3") (pin "1") (pinfunction "G_1") (pintype "passive"))
      (node (ref "R53") (pin "1") (pinfunction "1_1") (pintype "passive"))
    )
    (net (code "77") (name "Net-(Q4-D)") (class "Default")
      (node (ref "Q4") (pin "3") (pinfunction "D_3") (pintype "passive"))
      (node (ref "R61") (pin "1") (pinfunction "1_1") (pintype "passive"))
    )
    (net (code "78") (name "Net-(Q4-G)") (class "Default")
      (node (ref "Q4") (pin "1") (pinfunction "G_1") (pintype "passive"))
      (node (ref "R54") (pin "1") (pinfunction "1_1") (pintype "passive"))
    )
    (net (code "79") (name "Net-(Q5-G)") (class "Default")
      (node (ref "Q5") (pin "1") (pinfunction "G_1") (pintype "passive"))
      (node (ref "Q9") (pin "3") (pinfunction "D_3") (pintype "passive"))
      (node (ref "R71") (pin "2") (pinfunction "2_2") (pintype "passive"))
    )
    (net (code "80") (name "Net-(Q9-G)") (class "Default")
      (node (ref "Q9") (pin "1") (pinfunction "G_1") (pintype "passive"))
      (node (ref "R62") (pin "2") (pinfunction "2_2") (pintype "passive"))
    )
    (net (code "81") (name "Net-(Q10-D)") (class "Default")
      (node (ref "Q10") (pin "3") (pinfunction "D_3") (pintype "passive"))
      (node (ref "R62") (pin "1") (pinfunction "1_1") (pintype "passive"))
      (node (ref "R65") (pin "1") (pinfunction "1_1") (pintype "passive"))
    )
    (net (code "82") (name "Net-(Q10-G)") (class "Default")
      (node (ref "Q10") (pin "1") (pinfunction "G_1") (pintype "passive"))
      (node (ref "R69") (pin "2") (pinfunction "2_2") (pintype "passive"))
    )
    (net (code "83") (name "Net-(Q11-D)") (class "Default")
      (node (ref "Q11") (pin "3") (pinfunction "D_3") (pintype "passive"))
      (node (ref "Q6") (pin "1") (pinfunction "G_1") (pintype "passive"))
      (node (ref "R94") (pin "2") (pinfunction "2_2") (pintype "passive"))
    )
    (net (code "84") (name "Net-(Q11-G)") (class "Default")
      (node (ref "Q11") (pin "1") (pinfunction "G_1") (pintype "passive"))
      (node (ref "R107") (pin "2") (pinfunction "2_2") (pintype "passive"))
    )
    (net (code "85") (name "Net-(Q12-D)") (class "Default")
      (node (ref "Q12") (pin "3") (pinfunction "D_3") (pintype "passive"))
      (node (ref "R107") (pin "1") (pinfunction "1_1") (pintype "passive"))
      (node (ref "R63") (pin "1") (pinfunction "1_1") (pintype "passive"))
    )
    (net (code "86") (name "Net-(Q12-G)") (class "Default")
      (node (ref "Q12") (pin "1") (pinfunction "G_1") (pintype "passive"))
      (node (ref "R68") (pin "2") (pinfunction "2_2") (pintype "passive"))
    )
    (net (code "87") (name "Net-(U1-CP1)") (class "Default")
      (node (ref "C1") (pin "2") (pinfunction "2_2") (pintype "passive"))
      (node (ref "U1") (pin "4") (pinfunction "CP1_4") (pintype "passive"))
    )
    (net (code "88") (name "Net-(U1-CP2)") (class "Default")
      (node (ref "C1") (pin "1") (pinfunction "1_1") (pintype "passive"))
      (node (ref "U1") (pin "5") (pinfunction "CP2_5") (pintype "passive"))
    )
    (net (code "89") (name "Net-(U1-MS1)") (class "Default")
      (node (ref "R1") (pin "1") (pinfunction "1_1") (pintype "passive"))
      (node (ref "R28") (pin "2") (pinfunction "2_2") (pintype "passive"))
      (node (ref "U1") (pin "9") (pinfunction "MS1_9") (pintype "input"))
    )
    (net (code "90") (name "Net-(U1-MS2)") (class "Default")
      (node (ref "R2") (pin "1") (pinfunction "1_1") (pintype "passive"))
      (node (ref "U1") (pin "10") (pinfunction "MS2_10") (pintype "input"))
    )
    (net (code "91") (name "Net-(U1-MS3)") (class "Default")
      (node (ref "R3") (pin "1") (pinfunction "1_1") (pintype "passive"))
      (node (ref "U1") (pin "11") (pinfunction "MS3_11") (pintype "input"))
    )
    (net (code "92") (name "Net-(U1-ROSC)") (class "Default")
      (node (ref "R26") (pin "2") (pinfunction "2_2") (pintype "passive"))
      (node (ref "U1") (pin "13") (pinfunction "ROSC_13") (pintype "passive"))
    )
    (net (code "93") (name "Net-(U1-SENSE1)") (class "Default")
      (node (ref "R21") (pin "2") (pinfunction "2_2") (pintype "passive"))
      (node (ref "U1") (pin "23") (pinfunction "SENSE1_23") (pintype "passive"))
    )
    (net (code "94") (name "Net-(U1-SENSE2)") (class "Default")
      (node (ref "R20") (pin "2") (pinfunction "2_2") (pintype "passive"))
      (node (ref "U1") (pin "27") (pinfunction "SENSE2_27") (pintype "passive"))
    )
    (net (code "95") (name "Net-(U1-SLEEP)") (class "Default")
      (node (ref "R6") (pin "1") (pinfunction "1_1") (pintype "passive"))
      (node (ref "U1") (pin "14") (pinfunction "SLEEP_14") (pintype "passive"))
    )
    (net (code "96") (name "Net-(U1-VCP)") (class "Default")
      (node (ref "C13") (pin "1") (pinfunction "1_1") (pintype "passive"))
      (node (ref "U1") (pin "6") (pinfunction "VCP_6") (pintype "passive"))
    )
    (net (code "97") (name "Net-(U1-VREG)") (class "Default")
      (node (ref "C15") (pin "2") (pinfunction "2_2") (pintype "passive"))
      (node (ref "U1") (pin "8") (pinfunction "VREG_8") (pintype "passive"))
    )
    (net (code "98") (name "Net-(U2-CP1)") (class "Default")
      (node (ref "C2") (pin "1") (pinfunction "1_1") (pintype "passive"))
      (node (ref "U2") (pin "4") (pinfunction "CP1_4") (pintype "passive"))
    )
    (net (code "99") (name "Net-(U2-CP2)") (class "Default")
      (node (ref "C2") (pin "2") (pinfunction "2_2") (pintype "passive"))
      (node (ref "U2") (pin "5") (pinfunction "CP2_5") (pintype "passive"))
    )
    (net (code "100") (name "Net-(U2-MS1)") (class "Default")
      (node (ref "R29") (pin "2") (pinfunction "2_2") (pintype "passive"))
      (node (ref "R7") (pin "1") (pinfunction "1_1") (pintype "passive"))
      (node (ref "U2") (pin "9") (pinfunction "MS1_9") (pintype "input"))
    )
    (net (code "101") (name "Net-(U2-MS2)") (class "Default")
      (node (ref "R8") (pin "1") (pinfunction "1_1") (pintype "passive"))
      (node (ref "U2") (pin "10") (pinfunction "MS2_10") (pintype "input"))
    )
    (net (code "102") (name "Net-(U2-MS3)") (class "Default")
      (node (ref "R9") (pin "1") (pinfunction "1_1") (pintype "passive"))
      (node (ref "U2") (pin "11") (pinfunction "MS3_11") (pintype "input"))
    )
    (net (code "103") (name "Net-(U2-ROSC)") (class "Default")
      (node (ref "R27") (pin "2") (pinfunction "2_2") (pintype "passive"))
      (node (ref "U2") (pin "13") (pinfunction "ROSC_13") (pintype "passive"))
    )
    (net (code "104") (name "Net-(U2-SENSE1)") (class "Default")
      (node (ref "R23") (pin "2") (pinfunction "2_2") (pintype "passive"))
      (node (ref "U2") (pin "23") (pinfunction "SENSE1_23") (pintype "passive"))
    )
    (net (code "105") (name "Net-(U2-SENSE2)") (class "Default")
      (node (ref "R22") (pin "2") (pinfunction "2_2") (pintype "passive"))
      (node (ref "U2") (pin "27") (pinfunction "SENSE2_27") (pintype "passive"))
    )
    (net (code "106") (name "Net-(U2-SLEEP)") (class "Default")
      (node (ref "R12") (pin "1") (pinfunction "1_1") (pintype "passive"))
      (node (ref "U2") (pin "14") (pinfunction "SLEEP_14") (pintype "passive"))
    )
    (net (code "107") (name "Net-(U2-VCP)") (class "Default")
      (node (ref "C14") (pin "1") (pinfunction "1_1") (pintype "passive"))
      (node (ref "U2") (pin "6") (pinfunction "VCP_6") (pintype "passive"))
    )
    (net (code "108") (name "Net-(U2-VREG)") (class "Default")
      (node (ref "C16") (pin "2") (pinfunction "2_2") (pintype "passive"))
      (node (ref "U2") (pin "8") (pinfunction "VREG_8") (pintype "passive"))
    )
    (net (code "109") (name "Net-(U3-CP1)") (class "Default")
      (node (ref "C19") (pin "2") (pinfunction "2_2") (pintype "passive"))
      (node (ref "U3") (pin "4") (pinfunction "CP1_4") (pintype "passive"))
    )
    (net (code "110") (name "Net-(U3-CP2)") (class "Default")
      (node (ref "C19") (pin "1") (pinfunction "1_1") (pintype "passive"))
      (node (ref "U3") (pin "5") (pinfunction "CP2_5") (pintype "passive"))
    )
    (net (code "111") (name "Net-(U3-MS1)") (class "Default")
      (node (ref "R30") (pin "1") (pinfunction "1_1") (pintype "passive"))
      (node (ref "R56") (pin "2") (pinfunction "2_2") (pintype "passive"))
      (node (ref "U3") (pin "9") (pinfunction "MS1_9") (pintype "input"))
    )
    (net (code "112") (name "Net-(U3-MS2)") (class "Default")
      (node (ref "R31") (pin "1") (pinfunction "1_1") (pintype "passive"))
      (node (ref "U3") (pin "10") (pinfunction "MS2_10") (pintype "input"))
    )
    (net (code "113") (name "Net-(U3-MS3)") (class "Default")
      (node (ref "R32") (pin "1") (pinfunction "1_1") (pintype "passive"))
      (node (ref "U3") (pin "11") (pinfunction "MS3_11") (pintype "input"))
    )
    (net (code "114") (name "Net-(U3-ROSC)") (class "Default")
      (node (ref "R55") (pin "2") (pinfunction "2_2") (pintype "passive"))
      (node (ref "U3") (pin "13") (pinfunction "ROSC_13") (pintype "passive"))
    )
    (net (code "115") (name "Net-(U3-SENSE1)") (class "Default")
      (node (ref "R50") (pin "2") (pinfunction "2_2") (pintype "passive"))
      (node (ref "U3") (pin "23") (pinfunction "SENSE1_23") (pintype "passive"))
    )
    (net (code "116") (name "Net-(U3-SENSE2)") (class "Default")
      (node (ref "R49") (pin "2") (pinfunction "2_2") (pintype "passive"))
      (node (ref "U3") (pin "27") (pinfunction "SENSE2_27") (pintype "passive"))
    )
    (net (code "117") (name "Net-(U3-SLEEP)") (class "Default")
      (node (ref "R35") (pin "1") (pinfunction "1_1") (pintype "passive"))
      (node (ref "U3") (pin "14") (pinfunction "SLEEP_14") (pintype "passive"))
    )
    (net (code "118") (name "Net-(U3-VCP)") (class "Default")
      (node (ref "C30") (pin "1") (pinfunction "1_1") (pintype "passive"))
      (node (ref "U3") (pin "6") (pinfunction "VCP_6") (pintype "passive"))
    )
    (net (code "119") (name "Net-(U3-VREG)") (class "Default")
      (node (ref "C33") (pin "2") (pinfunction "2_2") (pintype "passive"))
      (node (ref "U3") (pin "8") (pinfunction "VREG_8") (pintype "passive"))
    )
    (net (code "120") (name "Net-(U4-CP1)") (class "Default")
      (node (ref "C20") (pin "1") (pinfunction "1_1") (pintype "passive"))
      (node (ref "U4") (pin "4") (pinfunction "CP1_4") (pintype "passive"))
    )
    (net (code "121") (name "Net-(U4-CP2)") (class "Default")
      (node (ref "C20") (pin "2") (pinfunction "2_2") (pintype "passive"))
      (node (ref "U4") (pin "5") (pinfunction "CP2_5") (pintype "passive"))
    )
    (net (code "122") (name "Net-(U4-MS1)") (class "Default")
      (node (ref "R36") (pin "1") (pinfunction "1_1") (pintype "passive"))
      (node (ref "R58") (pin "2") (pinfunction "2_2") (pintype "passive"))
      (node (ref "U4") (pin "9") (pinfunction "MS1_9") (pintype "input"))
    )
    (net (code "123") (name "Net-(U4-MS2)") (class "Default")
      (node (ref "R37") (pin "1") (pinfunction "1_1") (pintype "passive"))
      (node (ref "U4") (pin "10") (pinfunction "MS2_10") (pintype "input"))
    )
    (net (code "124") (name "Net-(U4-MS3)") (class "Default")
      (node (ref "R38") (pin "1") (pinfunction "1_1") (pintype "passive"))
      (node (ref "U4") (pin "11") (pinfunction "MS3_11") (pintype "input"))
    )
    (net (code "125") (name "Net-(U4-ROSC)") (class "Default")
      (node (ref "R57") (pin "2") (pinfunction "2_2") (pintype "passive"))
      (node (ref "U4") (pin "13") (pinfunction "ROSC_13") (pintype "passive"))
    )
    (net (code "126") (name "Net-(U4-SENSE1)") (class "Default")
      (node (ref "R52") (pin "2") (pinfunction "2_2") (pintype "passive"))
      (node (ref "U4") (pin "23") (pinfunction "SENSE1_23") (pintype "passive"))
    )
    (net (code "127") (name "Net-(U4-SENSE2)") (class "Default")
      (node (ref "R51") (pin "2") (pinfunction "2_2") (pintype "passive"))
      (node (ref "U4") (pin "27") (pinfunction "SENSE2_27") (pintype "passive"))
    )
    (net (code "128") (name "Net-(U4-SLEEP)") (class "Default")
      (node (ref "R41") (pin "1") (pinfunction "1_1") (pintype "passive"))
      (node (ref "U4") (pin "14") (pinfunction "SLEEP_14") (pintype "passive"))
    )
    (net (code "129") (name "Net-(U4-VCP)") (class "Default")
      (node (ref "C32") (pin "1") (pinfunction "1_1") (pintype "passive"))
      (node (ref "U4") (pin "6") (pinfunction "VCP_6") (pintype "passive"))
    )
    (net (code "130") (name "Net-(U4-VREG)") (class "Default")
      (node (ref "C34") (pin "2") (pinfunction "2_2") (pintype "passive"))
      (node (ref "U4") (pin "8") (pinfunction "VREG_8") (pintype "passive"))
    )
    (net (code "131") (name "V3.3") (class "Default")
      (node (ref "C21") (pin "2") (pinfunction "2_2") (pintype "passive"))
      (node (ref "C22") (pin "2") (pinfunction "2_2") (pintype "passive"))
      (node (ref "C23") (pin "2") (pinfunction "2_2") (pintype "passive"))
      (node (ref "C24") (pin "2") (pinfunction "2_2") (pintype "passive"))
      (node (ref "C3") (pin "2") (pinfunction "2_2") (pintype "passive"))
      (node (ref "C4") (pin "2") (pinfunction "2_2") (pintype "passive"))
      (node (ref "C5") (pin "2") (pinfunction "2_2") (pintype "passive"))
      (node (ref "C6") (pin "2") (pinfunction "2_2") (pintype "passive"))
      (node (ref "D2") (pin "2") (pinfunction "A_2") (pintype "passive"))
      (node (ref "D3") (pin "2") (pinfunction "A_2") (pintype "passive"))
      (node (ref "D5") (pin "2") (pinfunction "A_2") (pintype "passive"))
      (node (ref "D6") (pin "2") (pinfunction "A_2") (pintype "passive"))
      (node (ref "J12") (pin "1") (pinfunction "1_1") (pintype "passive"))
      (node (ref "J13") (pin "1") (pinfunction "1_1") (pintype "passive"))
      (node (ref "J14") (pin "1") (pinfunction "1_1") (pintype "passive"))
      (node (ref "J15") (pin "1") (pinfunction "1_1") (pintype "passive"))
      (node (ref "R1") (pin "2") (pinfunction "2_2") (pintype "passive"))
      (node (ref "R104") (pin "2") (pinfunction "2_2") (pintype "passive"))
      (node (ref "R12") (pin "2") (pinfunction "2_2") (pintype "passive"))
      (node (ref "R13") (pin "2") (pinfunction "2_2") (pintype "passive"))
      (node (ref "R18") (pin "2") (pinfunction "2_2") (pintype "passive"))
      (node (ref "R19") (pin "2") (pinfunction "2_2") (pintype "passive"))
      (node (ref "R2") (pin "2") (pinfunction "2_2") (pintype "passive"))
      (node (ref "R3") (pin "2") (pinfunction "2_2") (pintype "passive"))
      (node (ref "R30") (pin "2") (pinfunction "2_2") (pintype "passive"))
      (node (ref "R31") (pin "2") (pinfunction "2_2") (pintype "passive"))
      (node (ref "R32") (pin "2") (pinfunction "2_2") (pintype "passive"))
      (node (ref "R35") (pin "2") (pinfunction "2_2") (pintype "passive"))
      (node (ref "R36") (pin "2") (pinfunction "2_2") (pintype "passive"))
      (node (ref "R37") (pin "2") (pinfunction "2_2") (pintype "passive"))
      (node (ref "R38") (pin "2") (pinfunction "2_2") (pintype "passive"))
      (node (ref "R41") (pin "2") (pinfunction "2_2") (pintype "passive"))
      (node (ref "R42") (pin "2") (pinfunction "2_2") (pintype "passive"))
      (node (ref "R45") (pin "2") (pinfunction "2_2") (pintype "passive"))
      (node (ref "R47") (pin "2") (pinfunction "2_2") (pintype "passive"))
      (node (ref "R48") (pin "2") (pinfunction "2_2") (pintype "passive"))
      (node (ref "R6") (pin "2") (pinfunction "2_2") (pintype "passive"))
      (node (ref "R64") (pin "2") (pinfunction "2_2") (pintype "passive"))
      (node (ref "R7") (pin "2") (pinfunction "2_2") (pintype "passive"))
      (node (ref "R8") (pin "2") (pinfunction "2_2") (pintype "passive"))
      (node (ref "R9") (pin "2") (pinfunction "2_2") (pintype "passive"))
      (node (ref "R97") (pin "2") (pinfunction "2_2") (pintype "passive"))
      (node (ref "U1") (pin "15") (pinfunction "VDD_15") (pintype "passive"))
      (node (ref "U2") (pin "15") (pinfunction "VDD_15") (pintype "passive"))
      (node (ref "U3") (pin "15") (pinfunction "VDD_15") (pintype "passive"))
      (node (ref "U4") (pin "15") (pinfunction "VDD_15") (pintype "passive"))
    )
    (net (code "132") (name "V5") (class "Default")
      (node (ref "J17") (pin "2") (pinfunction "2_2") (pintype "passive"))
      (node (ref "J3") (pin "1") (pinfunction "1_1") (pintype "passive"))
      (node (ref "J3") (pin "2") (pinfunction "2_2") (pintype "passive"))
      (node (ref "J6") (pin "1") (pinfunction "1_1") (pintype "passive"))
      (node (ref "J6") (pin "2") (pinfunction "2_2") (pintype "passive"))
      (node (ref "J9") (pin "1") (pinfunction "1_1") (pintype "passive"))
      (node (ref "J9") (pin "2") (pinfunction "2_2") (pintype "passive"))
    )
    (net (code "133") (name "VA3.3") (class "Default")
      (node (ref "R59") (pin "2") (pinfunction "2_2") (pintype "passive"))
      (node (ref "R60") (pin "2") (pinfunction "2_2") (pintype "passive"))
    )
    (net (code "134") (name "VMM") (class "Default")
      (node (ref "C10") (pin "2") (pinfunction "2_2") (pintype "passive"))
      (node (ref "C11") (pin "1") (pinfunction "1_1") (pintype "passive"))
      (node (ref "C12") (pin "1") (pinfunction "1_1") (pintype "passive"))
      (node (ref "C13") (pin "2") (pinfunction "2_2") (pintype "passive"))
      (node (ref "C14") (pin "2") (pinfunction "2_2") (pintype "passive"))
      (node (ref "C25") (pin "2") (pinfunction "2_2") (pintype "passive"))
      (node (ref "C26") (pin "2") (pinfunction "2_2") (pintype "passive"))
      (node (ref "C27") (pin "1") (pinfunction "1_1") (pintype "passive"))
      (node (ref "C28") (pin "2") (pinfunction "2_2") (pintype "passive"))
      (node (ref "C29") (pin "2") (pinfunction "2_2") (pintype "passive"))
      (node (ref "C30") (pin "2") (pinfunction "2_2") (pintype "passive"))
      (node (ref "C31") (pin "1") (pinfunction "1_1") (pintype "passive"))
      (node (ref "C32") (pin "2") (pinfunction "2_2") (pintype "passive"))
      (node (ref "C62") (pin "2") (pinfunction "2_2") (pintype "passive"))
      (node (ref "C7") (pin "1") (pinfunction "1_1") (pintype "passive"))
      (node (ref "C8") (pin "2") (pinfunction "2_2") (pintype "passive"))
      (node (ref "C9") (pin "2") (pinfunction "2_2") (pintype "passive"))
      (node (ref "D15") (pin "1") (pinfunction "K_1") (pintype "passive"))
      (node (ref "D16") (pin "1") (pinfunction "K_1") (pintype "passive"))
      (node (ref "J21") (pin "1") (pinfunction "1_1") (pintype "passive"))
      (node (ref "J7") (pin "3") (pinfunction "3_3") (pintype "passive"))
      (node (ref "J8") (pin "3") (pinfunction "3_3") (pintype "passive"))
      (node (ref "R106") (pin "2") (pinfunction "2_2") (pintype "passive"))
      (node (ref "R43") (pin "2") (pinfunction "2_2") (pintype "passive"))
      (node (ref "R66") (pin "2") (pinfunction "2_2") (pintype "passive"))
      (node (ref "R67") (pin "2") (pinfunction "2_2") (pintype "passive"))
      (node (ref "U1") (pin "22") (pinfunction "VBB1_22") (pintype "passive"))
      (node (ref "U1") (pin "28") (pinfunction "VBB2_28") (pintype "passive"))
      (node (ref "U2") (pin "22") (pinfunction "VBB1_22") (pintype "passive"))
      (node (ref "U2") (pin "28") (pinfunction "VBB2_28") (pintype "passive"))
      (node (ref "U3") (pin "22") (pinfunction "VBB1_22") (pintype "passive"))
      (node (ref "U3") (pin "28") (pinfunction "VBB2_28") (pintype "passive"))
      (node (ref "U4") (pin "22") (pinfunction "VBB1_22") (pintype "passive"))
      (node (ref "U4") (pin "28") (pinfunction "VBB2_28") (pintype "passive"))
    )
    (net (code "135") (name "unconnected-(U1-NC-Pad7)") (class "Default")
      (node (ref "U1") (pin "7") (pinfunction "NC_7") (pintype "passive+no_connect"))
    )
    (net (code "136") (name "unconnected-(U1-NC-Pad20)") (class "Default")
      (node (ref "U1") (pin "20") (pinfunction "NC_20") (pintype "passive+no_connect"))
    )
    (net (code "137") (name "unconnected-(U1-NC-Pad25)") (class "Default")
      (node (ref "U1") (pin "25") (pinfunction "NC_25") (pintype "passive+no_connect"))
    )
    (net (code "138") (name "unconnected-(U2-NC-Pad7)") (class "Default")
      (node (ref "U2") (pin "7") (pinfunction "NC_7") (pintype "passive+no_connect"))
    )
    (net (code "139") (name "unconnected-(U2-NC-Pad20)") (class "Default")
      (node (ref "U2") (pin "20") (pinfunction "NC_20") (pintype "passive+no_connect"))
    )
    (net (code "140") (name "unconnected-(U2-NC-Pad25)") (class "Default")
      (node (ref "U2") (pin "25") (pinfunction "NC_25") (pintype "passive+no_connect"))
    )
    (net (code "141") (name "unconnected-(U3-NC-Pad7)") (class "Default")
      (node (ref "U3") (pin "7") (pinfunction "NC_7") (pintype "passive+no_connect"))
    )
    (net (code "142") (name "unconnected-(U3-NC-Pad20)") (class "Default")
      (node (ref "U3") (pin "20") (pinfunction "NC_20") (pintype "passive+no_connect"))
    )
    (net (code "143") (name "unconnected-(U3-NC-Pad25)") (class "Default")
      (node (ref "U3") (pin "25") (pinfunction "NC_25") (pintype "passive+no_connect"))
    )
    (net (code "144") (name "unconnected-(U4-NC-Pad7)") (class "Default")
      (node (ref "U4") (pin "7") (pinfunction "NC_7") (pintype "passive+no_connect"))
    )
    (net (code "145") (name "unconnected-(U4-NC-Pad20)") (class "Default")
      (node (ref "U4") (pin "20") (pinfunction "NC_20") (pintype "passive+no_connect"))
    )
    (net (code "146") (name "unconnected-(U4-NC-Pad25)") (class "Default")
      (node (ref "U4") (pin "25") (pinfunction "NC_25") (pintype "passive+no_connect"))
    )
  )
)
